# plugwatch.net
KiCad netlist of a schematic drawn in EAGLE
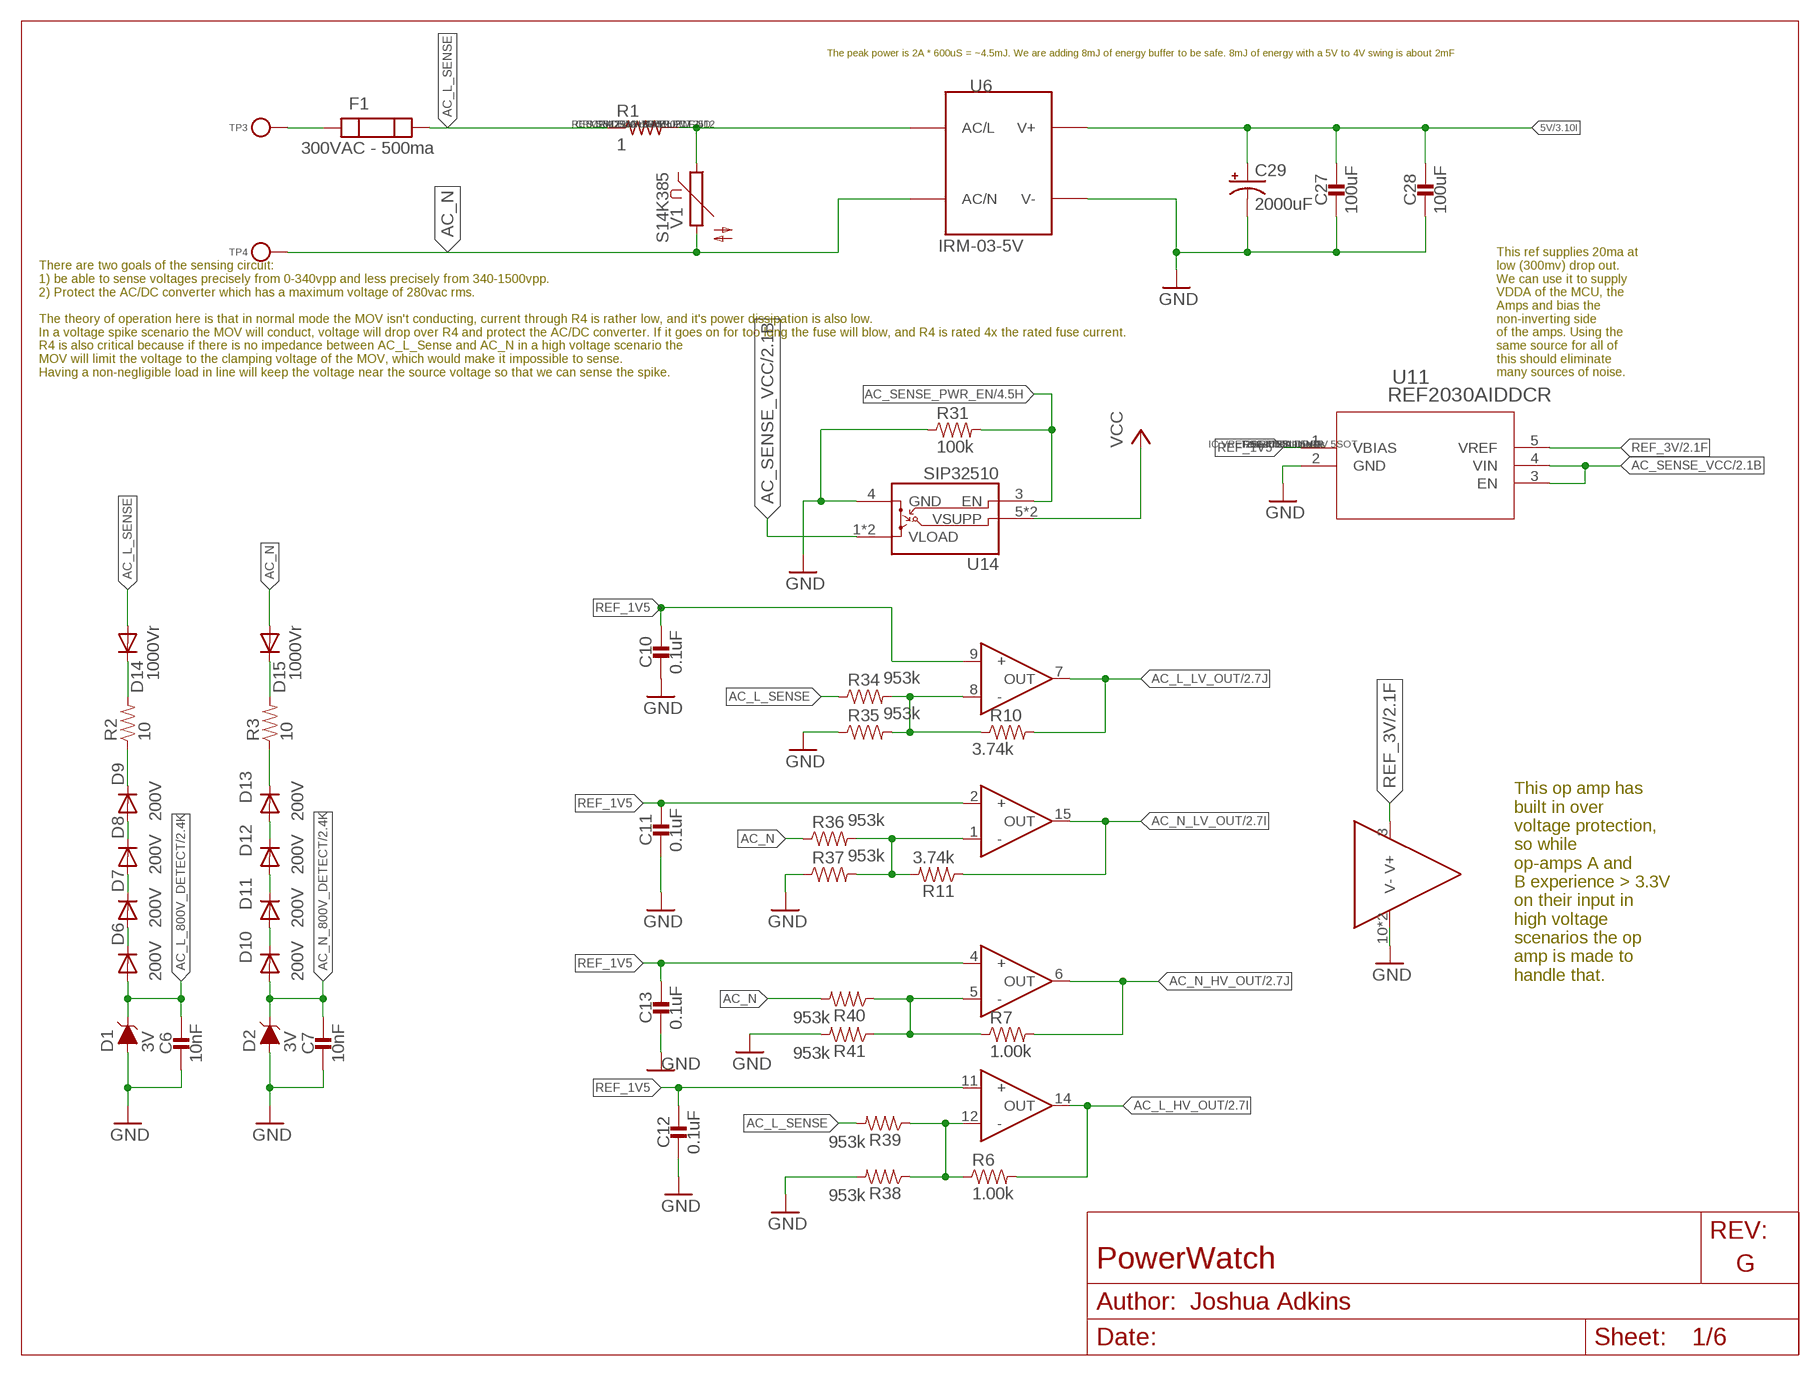
[diagram p0: schematic, sheet 1]
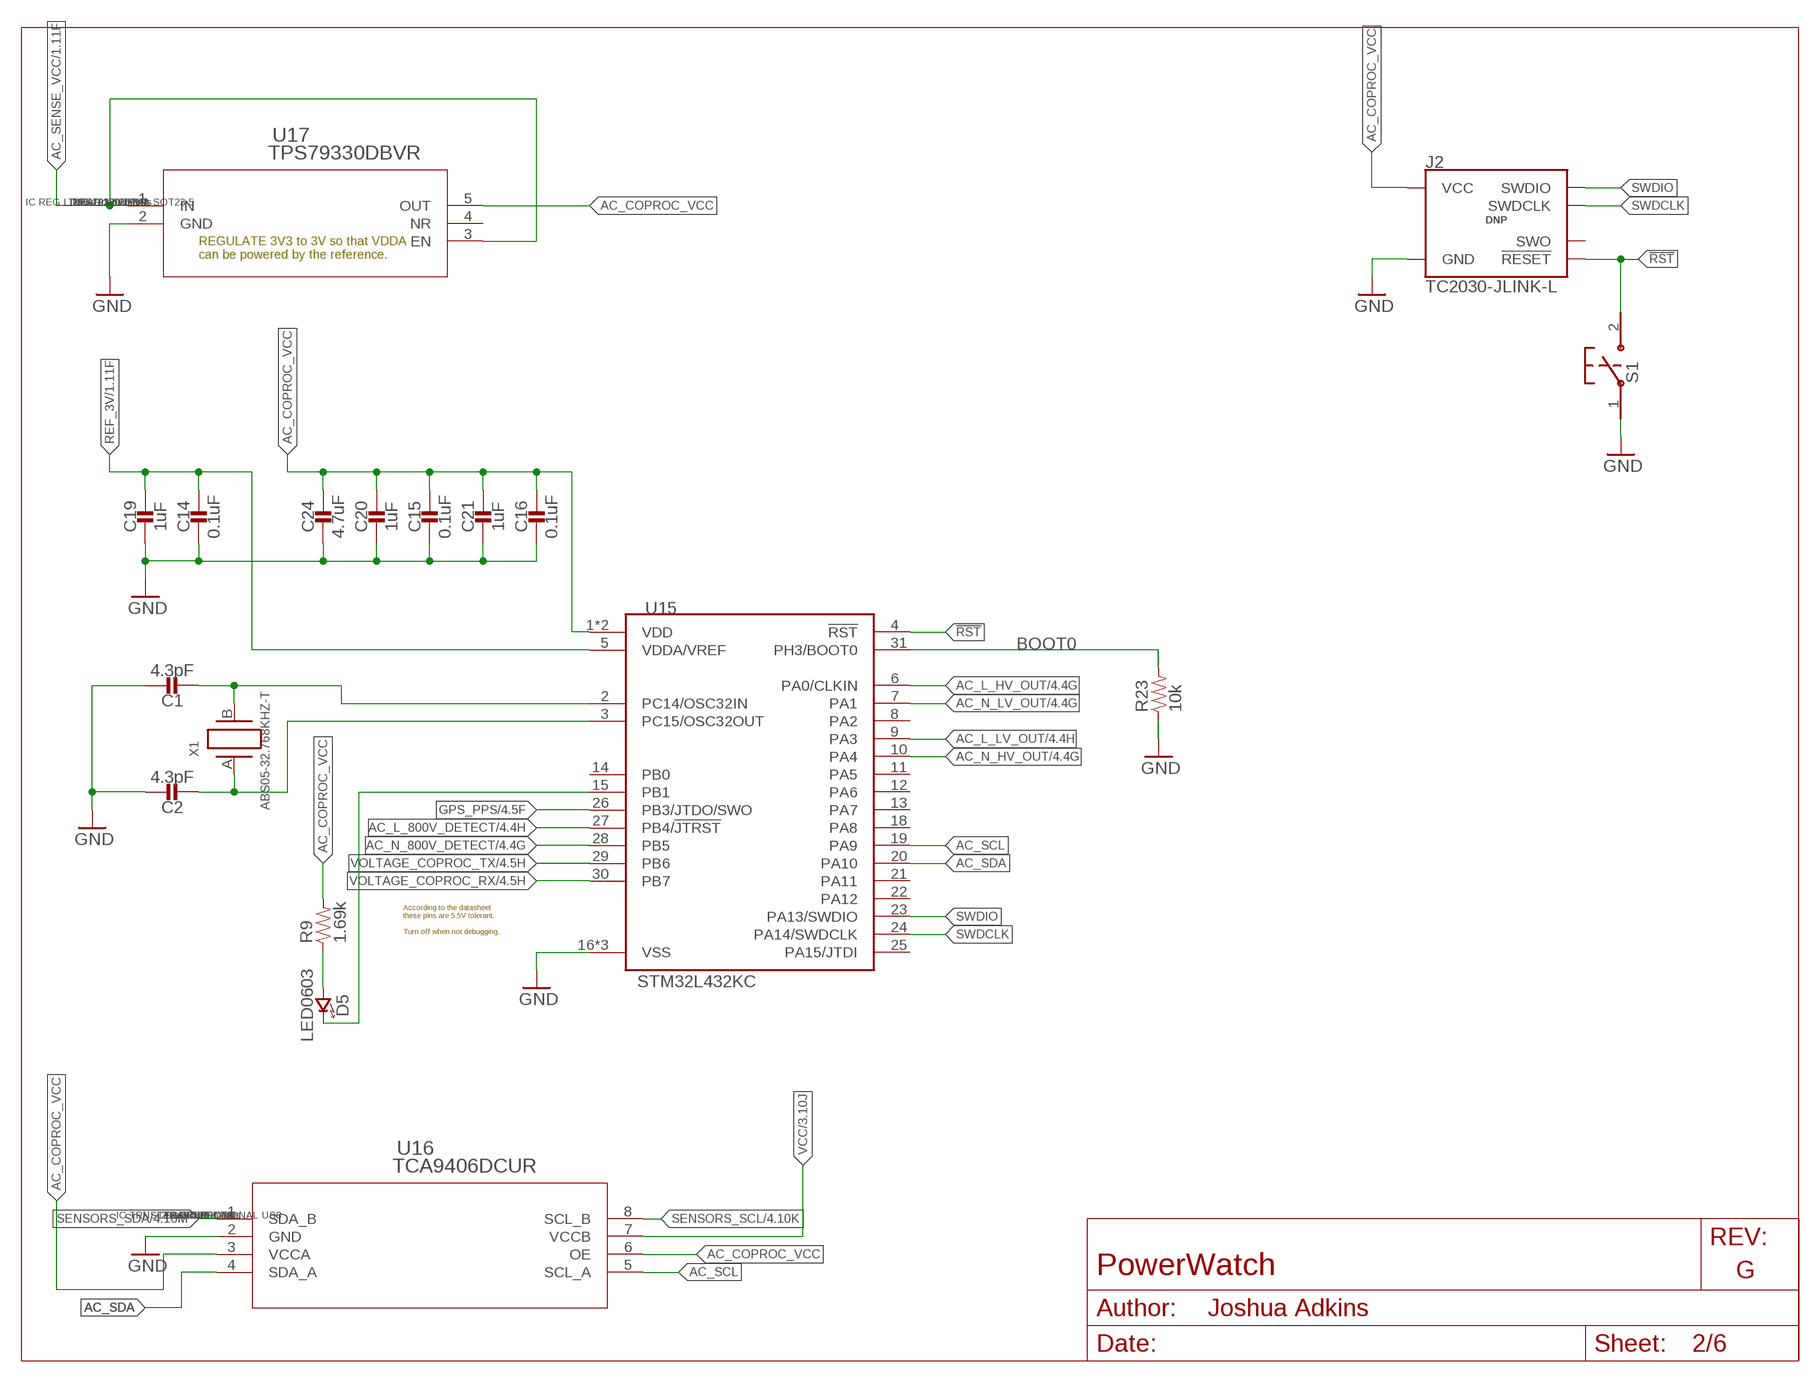
[diagram p1: schematic, sheet 2]
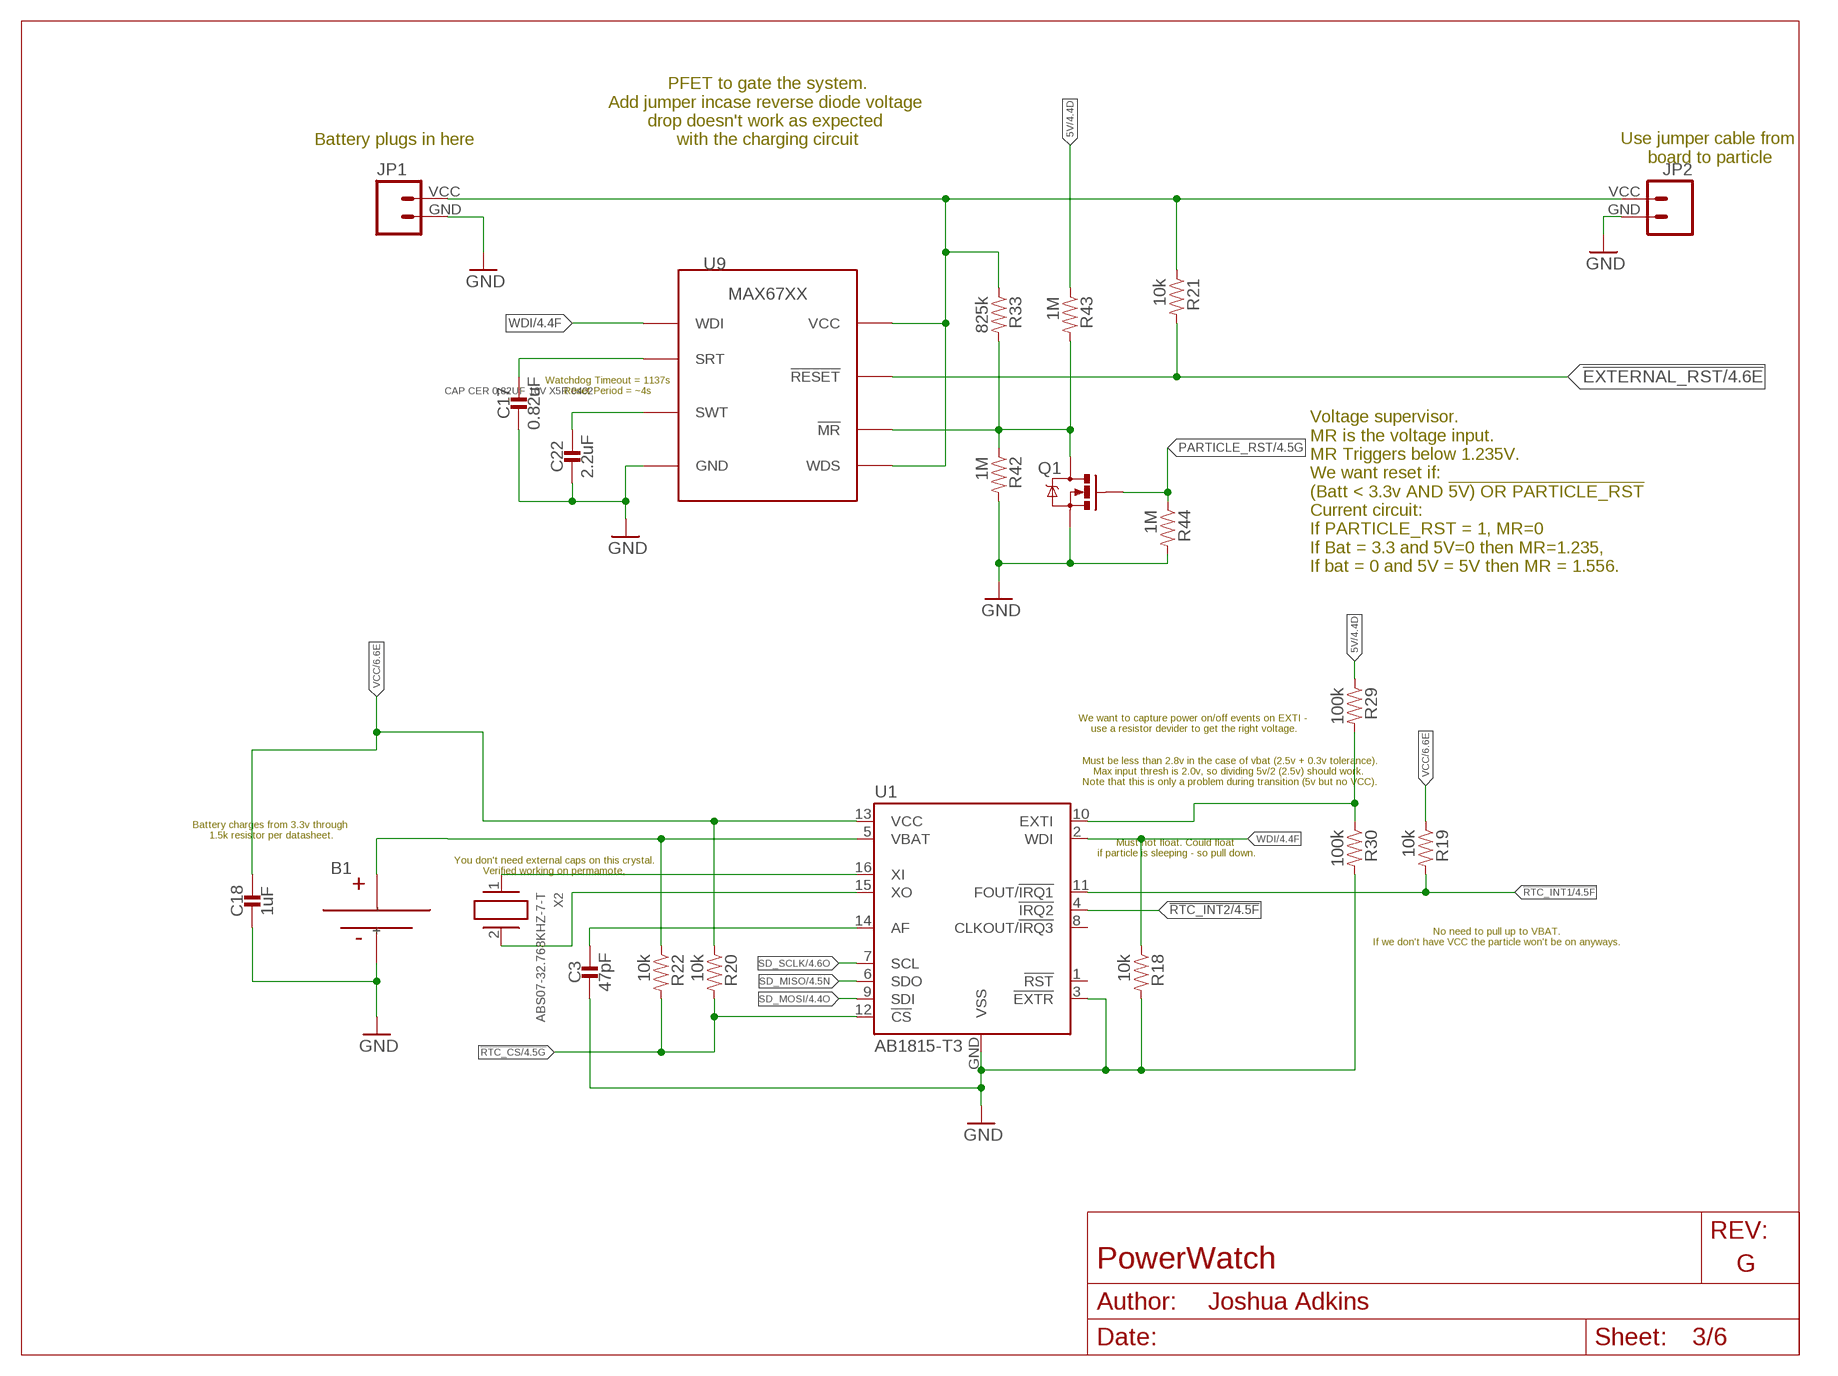
[diagram p2: schematic, sheet 3]
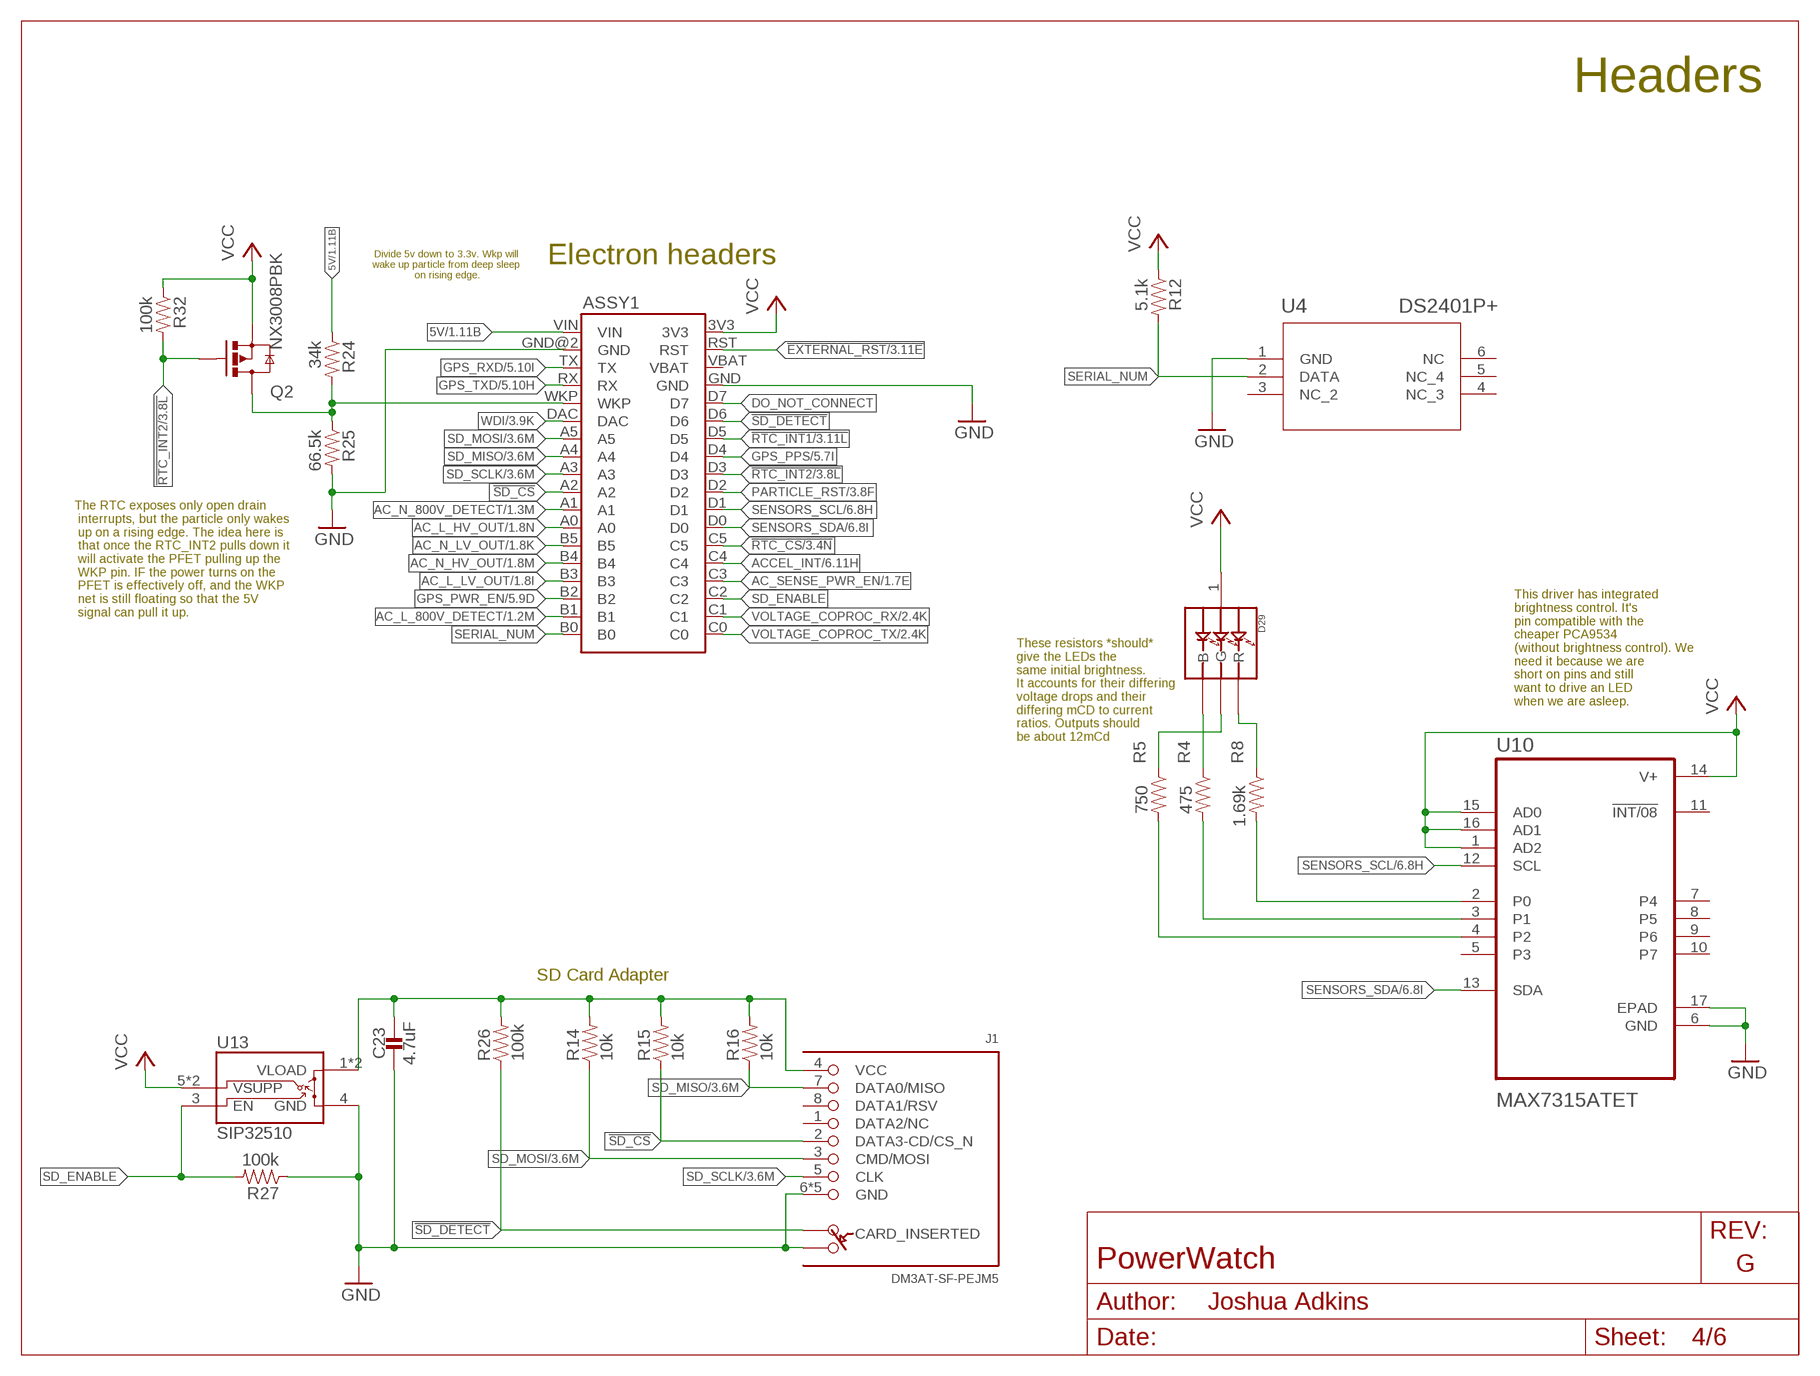
[diagram p3: schematic, sheet 4]
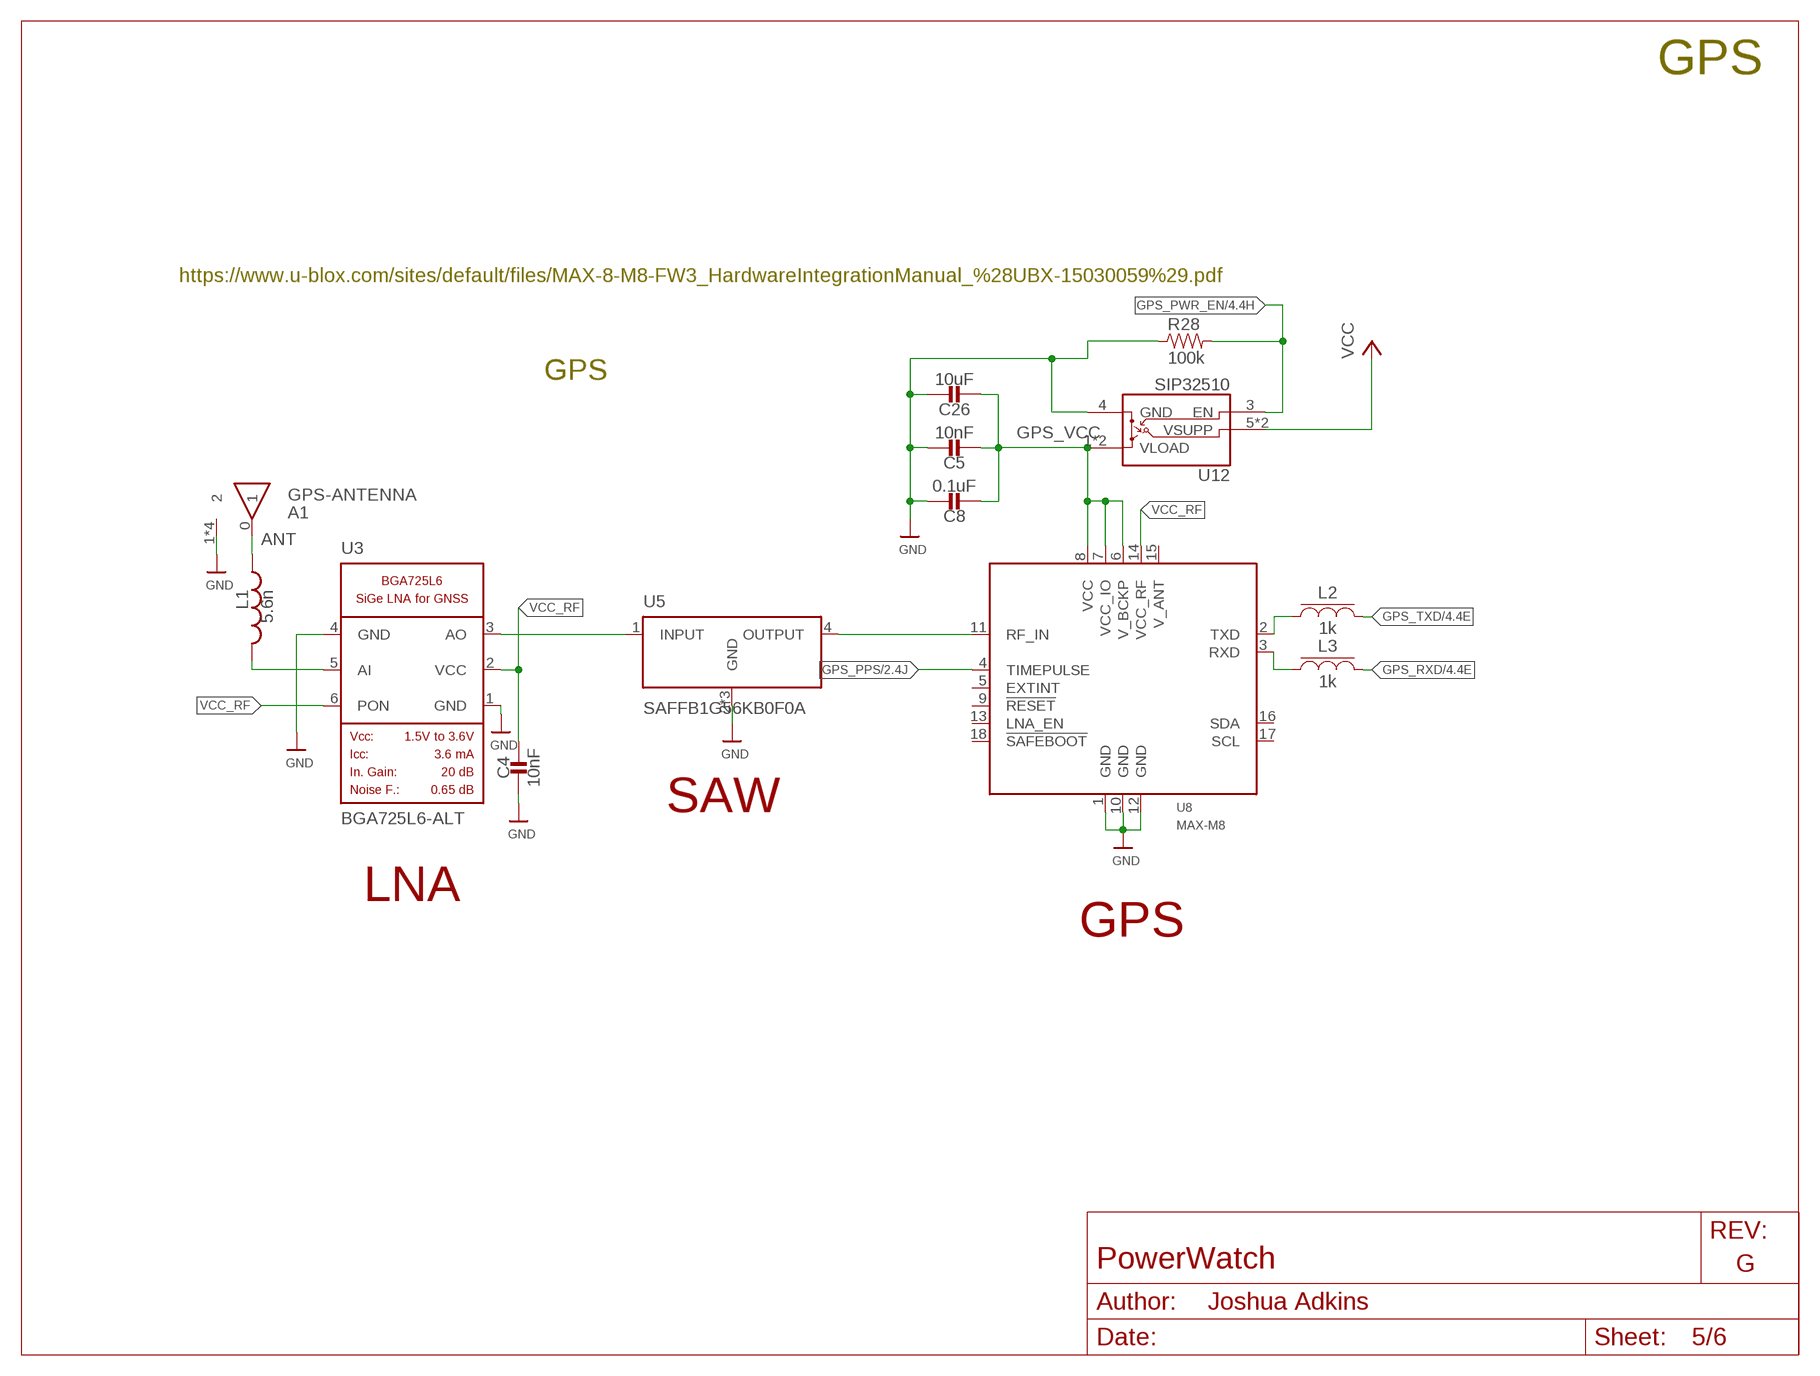
[diagram p4: schematic, sheet 5]
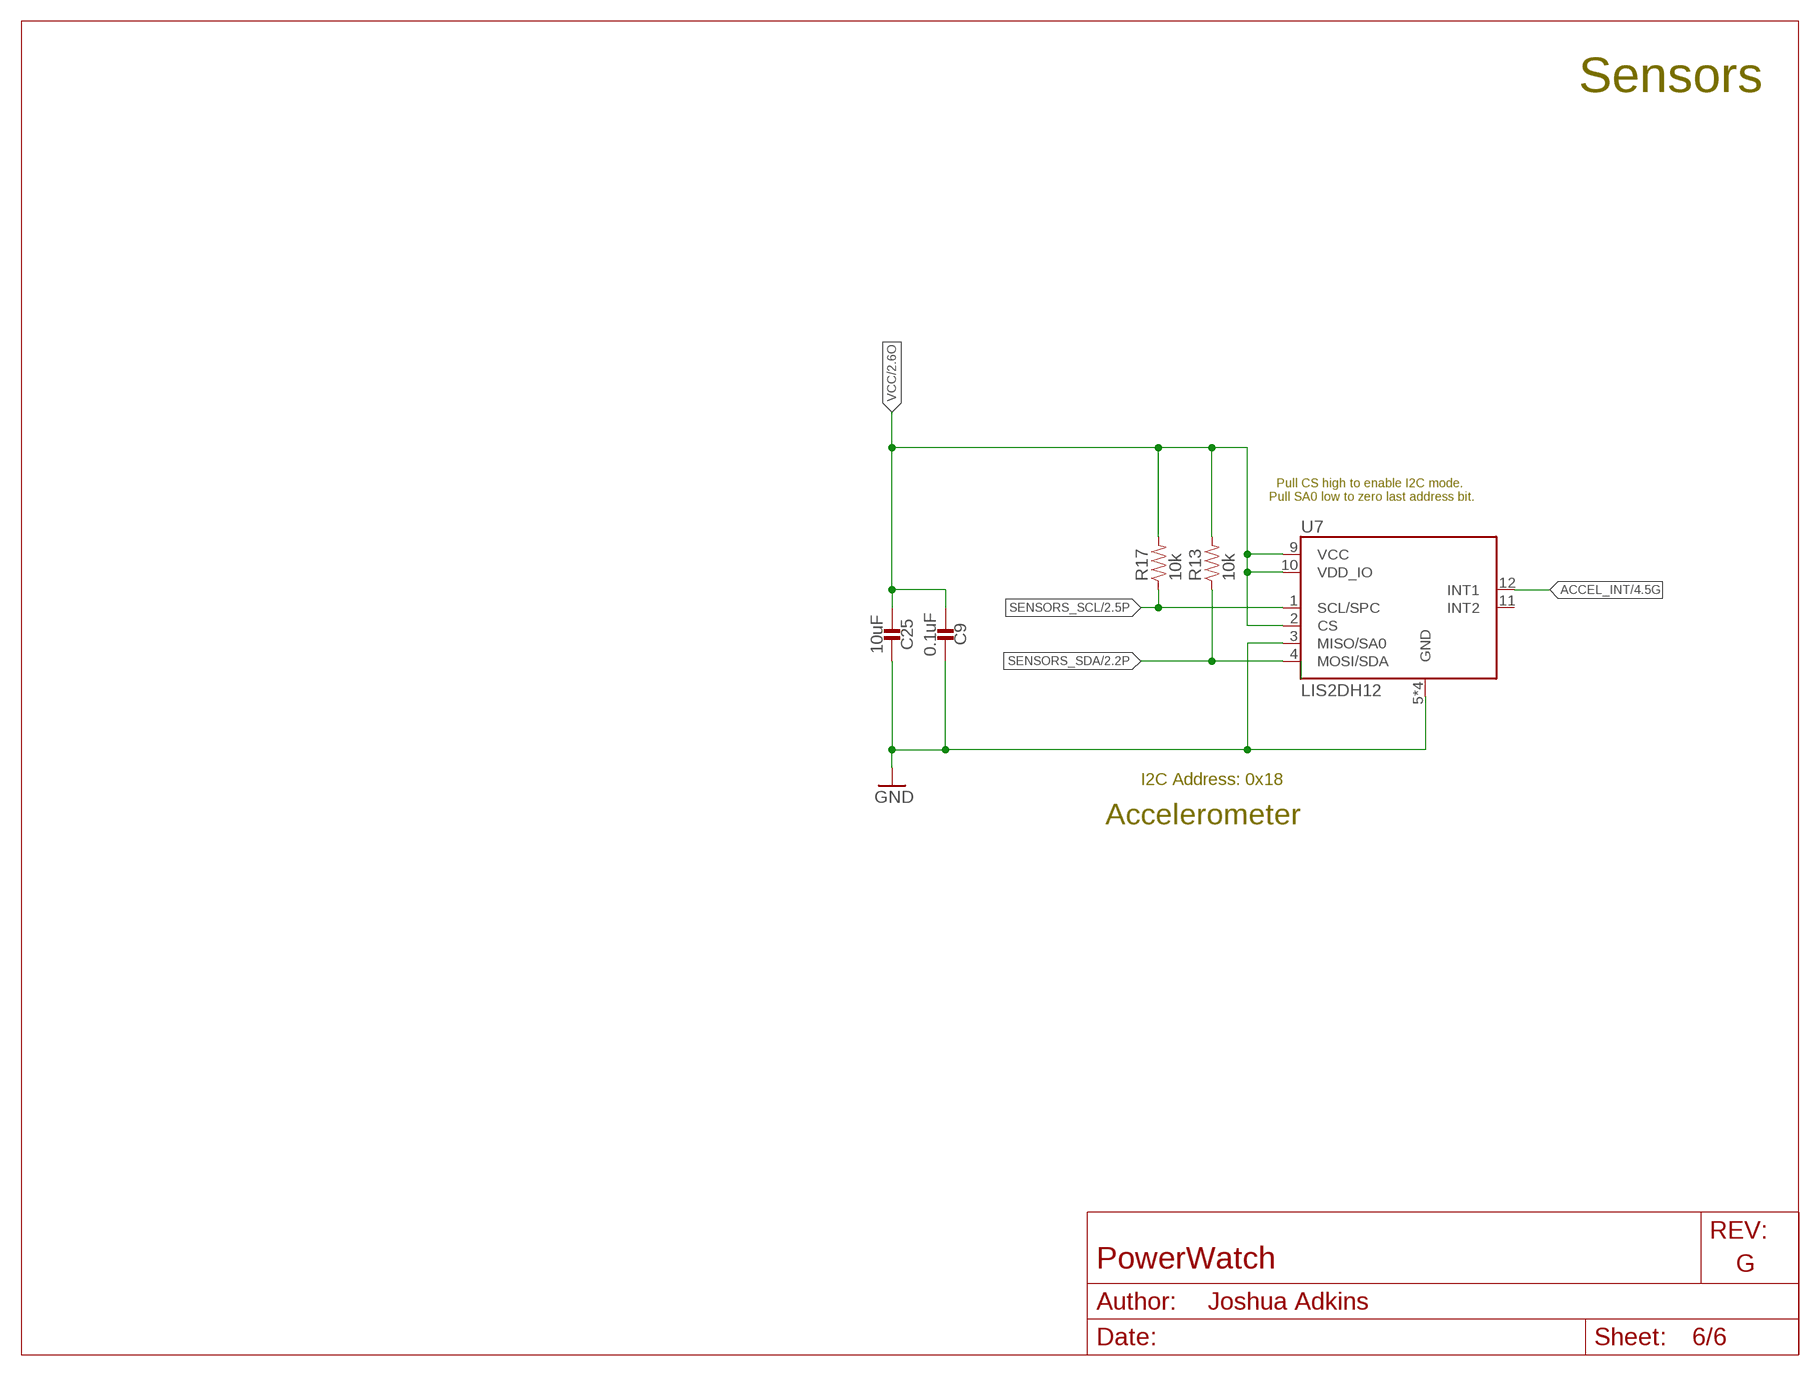
[diagram p5: schematic, sheet 6]

(export (version "E")
  (design (tool "Eeschema 10.0.6"))
  (components
    (comp (ref "ASSY1")
      (value "ELECTRON")
      (footprint "eagle-import:ELECTRON_SINGLE-ROW")
      (description "18 Position header")
      (fields (field (name "MANUFACTURER") "Sullins") (field (name "MPN") "PPPC181LFBN-RC"))
      (libsource (lib "eagle-import") (part "ELECTRON"))
    )
    (comp (ref "C23")
      (value "4.7uF")
      (footprint "eagle-import:0402_CAP")
      (description "CAP CER 4.7UF 6.3V X5R 0402")
      (fields (field (name "MANUFACTURER") "TDK Corporation ") (field (name "MPN") "C1005X5R0J475K050BC "))
      (libsource (lib "eagle-import") (part "CAPACITOR0402_CAP"))
    )
    (comp (ref "D29")
      (value "SML-LX0404SIUPGUSB")
      (footprint "eagle-import:1MM_SQ_4PAD")
      (fields (field (name "MANUFACTURER") "Lumex Opto"))
      (libsource (lib "eagle-import") (part "SML-LX0404SIUPGUSB"))
    )
    (comp (ref "J1")
      (value "DM3AT-SF-PEJM5")
      (footprint "eagle-import:DM3AT-SF-PEJM5")
      (fields (field (name "MANUFACTURER") "Hirose Electric Co Ltd"))
      (libsource (lib "eagle-import") (part "DM3AT-SF-PEJM5"))
    )
    (comp (ref "Q2")
      (value "NX3008PBK")
      (footprint "eagle-import:SOT23-3")
      (fields (field (name "MANUFACTURER") "Nexperia") (field (name "MPN") "NX3008PBK,215"))
      (libsource (lib "eagle-import") (part "NX3008PBK"))
    )
    (comp (ref "R4")
      (value "475")
      (footprint "eagle-import:0402_RES")
      (description "RES 475 OHM 1% 1/16W 0402")
      (fields (field (name "MANUFACTURER") "Stackpole Electronics Inc") (field (name "MPN") "RMCF0402FT475R"))
      (libsource (lib "eagle-import") (part "RESISTOR0402_RES"))
    )
    (comp (ref "R5")
      (value "750")
      (footprint "eagle-import:0402_RES")
      (description "RES SMD 750 OHM 1% 1/10W 0402")
      (fields
        (field (name "MANUFACTURER") "Panasonic Electronic Components")
        (field (name "MPN") "ERJ-2RKF7500X")
      )
      (libsource (lib "eagle-import") (part "RESISTOR0402_RES"))
    )
    (comp (ref "R8")
      (value "1.69k")
      (footprint "eagle-import:0402_RES")
      (description "RES SMD 1.69K OHM 1% 1/16W 0402")
      (fields (field (name "MANUFACTURER") "Yageo") (field (name "MPN") "RC0402FR-071K69L"))
      (libsource (lib "eagle-import") (part "RESISTOR0402_RES"))
    )
    (comp (ref "R12")
      (value "5.1k")
      (footprint "eagle-import:0402_RES")
      (description "RES SMD 5.1K OHM 1% 1/10W 0402")
      (fields
        (field (name "MANUFACTURER") "Panasonic Electronic Components")
        (field (name "MPN") "ERJ-2RKF5101X")
      )
      (libsource (lib "eagle-import") (part "RESISTOR0402_RES"))
    )
    (comp (ref "R14")
      (value "10k")
      (footprint "eagle-import:0402_RES")
      (description "RES SMD 10K OHM 1% 1/16W 0402")
      (fields
        (field (name "MANUFACTURER") "Stackpole Electronics Inc. ")
        (field (name "MPN") "RMCF0402FT10K0 ")
      )
      (libsource (lib "eagle-import") (part "RESISTOR0402_RES"))
    )
    (comp (ref "R15")
      (value "10k")
      (footprint "eagle-import:0402_RES")
      (description "RES SMD 10K OHM 1% 1/16W 0402")
      (fields
        (field (name "MANUFACTURER") "Stackpole Electronics Inc. ")
        (field (name "MPN") "RMCF0402FT10K0 ")
      )
      (libsource (lib "eagle-import") (part "RESISTOR0402_RES"))
    )
    (comp (ref "R16")
      (value "10k")
      (footprint "eagle-import:0402_RES")
      (description "RES SMD 10K OHM 1% 1/16W 0402")
      (fields
        (field (name "MANUFACTURER") "Stackpole Electronics Inc. ")
        (field (name "MPN") "RMCF0402FT10K0 ")
      )
      (libsource (lib "eagle-import") (part "RESISTOR0402_RES"))
    )
    (comp (ref "R24")
      (value "34k")
      (footprint "eagle-import:0402_RES")
      (description "RES SMD 34K OHM 1% 1/10W 0402")
      (fields
        (field (name "MANUFACTURER") "Panasonic Electronic Components")
        (field (name "MPN") "ERJ-2RKF3402X")
      )
      (libsource (lib "eagle-import") (part "RESISTOR0402_RES"))
    )
    (comp (ref "R25")
      (value "66.5k")
      (footprint "eagle-import:0402_RES")
      (description "RES SMD 66.5K OHM 1% 1/16W 0402")
      (fields (field (name "MANUFACTURER") "Yageo") (field (name "MPN") "RC0402FR-0766K5L"))
      (libsource (lib "eagle-import") (part "RESISTOR0402_RES"))
    )
    (comp (ref "R26")
      (value "100k")
      (footprint "eagle-import:0402_RES")
      (description "RES SMD 100K OHM 1% 1/16W 0402")
      (fields (field (name "MANUFACTURER") "Yageo") (field (name "MPN") "RC0402FR-07100KL"))
      (libsource (lib "eagle-import") (part "RESISTOR0402_RES"))
    )
    (comp (ref "R27")
      (value "100k")
      (footprint "eagle-import:0402_RES")
      (description "RES SMD 100K OHM 1% 1/16W 0402")
      (fields (field (name "MANUFACTURER") "Yageo") (field (name "MPN") "RC0402FR-07100KL"))
      (libsource (lib "eagle-import") (part "RESISTOR0402_RES"))
    )
    (comp (ref "R32")
      (value "100k")
      (footprint "eagle-import:0402_RES")
      (description "RES SMD 100K OHM 1% 1/16W 0402")
      (fields (field (name "MANUFACTURER") "Yageo") (field (name "MPN") "RC0402FR-07100KL"))
      (libsource (lib "eagle-import") (part "RESISTOR0402_RES"))
    )
    (comp (ref "U4")
      (value "DS2401P+")
      (footprint "eagle-import:21-0382")
      (fields (field (name "MANUFACTURER") "Maxim Integrated") (field (name "SPICEPREFIX") "X"))
      (libsource (lib "eagle-import") (part "DS2401P+"))
    )
    (comp (ref "U10")
      (value "MAX7315ATET")
      (footprint "eagle-import:QFN50P300X300X80-17N")
      (description "IC I/O EXPANDER I2C 8B 16TQFN")
      (fields
        (field (name "DIGI-KEY_PART_NUMBER") "MAX7315ATE+-ND")
        (field (name "MF") "Maxim Integrated")
        (field (name "MP") "MAX7315ATE+")
        (field (name "DIGIKEY") "MAX7315ATE+-ND")
        (field (name "MANUFACTURER") "Maxim Integrated")
        (field (name "MPN") "MAX7315ATE+")
      )
      (libsource (lib "eagle-import") (part "MAX7315ATET"))
    )
    (comp (ref "U13")
      (value "SIP32510")
      (footprint "eagle-import:TSOT23-6")
      (fields (field (name "MANUFACTURER") "Vishay") (field (name "MPN") "SIP32510DT-T1-GE3"))
      (libsource (lib "eagle-import") (part "SIP32510"))
    )
    (comp (ref "C1")
      (value "4.3pF")
      (footprint "eagle-import:0402_CAP")
      (description "CAP CER 4.3PF 50V C0G/NP0 0402")
      (fields
        (field (name "MANUFACTURER") "Murata Electronics North America")
        (field (name "MPN") "GJM1555C1H4R3CB01D")
      )
      (libsource (lib "eagle-import") (part "CAPACITOR0402_CAP"))
    )
    (comp (ref "C2")
      (value "4.3pF")
      (footprint "eagle-import:0402_CAP")
      (description "CAP CER 4.3PF 50V C0G/NP0 0402")
      (fields
        (field (name "MANUFACTURER") "Murata Electronics North America")
        (field (name "MPN") "GJM1555C1H4R3CB01D")
      )
      (libsource (lib "eagle-import") (part "CAPACITOR0402_CAP"))
    )
    (comp (ref "C14")
      (value "0.1uF")
      (footprint "eagle-import:0402_CAP")
      (description "CAP CER 0.1UF 10V X5R 0402")
      (fields (field (name "MANUFACTURER") "Yageo") (field (name "MPN") "CC0402KRX5R6BB104"))
      (libsource (lib "eagle-import") (part "CAPACITOR0402_CAP"))
    )
    (comp (ref "C15")
      (value "0.1uF")
      (footprint "eagle-import:0402_CAP")
      (description "CAP CER 0.1UF 10V X5R 0402")
      (fields (field (name "MANUFACTURER") "Yageo") (field (name "MPN") "CC0402KRX5R6BB104"))
      (libsource (lib "eagle-import") (part "CAPACITOR0402_CAP"))
    )
    (comp (ref "C16")
      (value "0.1uF")
      (footprint "eagle-import:0402_CAP")
      (description "CAP CER 0.1UF 10V X5R 0402")
      (fields (field (name "MANUFACTURER") "Yageo") (field (name "MPN") "CC0402KRX5R6BB104"))
      (libsource (lib "eagle-import") (part "CAPACITOR0402_CAP"))
    )
    (comp (ref "C19")
      (value "1uF")
      (footprint "eagle-import:0402_CAP")
      (description "CAP CER 1UF 10V X7S 0402")
      (fields
        (field (name "MANUFACTURER") "Murata Electronics North America")
        (field (name "MPN") "GCM155C71A105KE38D")
      )
      (libsource (lib "eagle-import") (part "CAPACITOR0402_CAP"))
    )
    (comp (ref "C20")
      (value "1uF")
      (footprint "eagle-import:0402_CAP")
      (description "CAP CER 1UF 10V X7S 0402")
      (fields
        (field (name "MANUFACTURER") "Murata Electronics North America")
        (field (name "MPN") "GCM155C71A105KE38D")
      )
      (libsource (lib "eagle-import") (part "CAPACITOR0402_CAP"))
    )
    (comp (ref "C21")
      (value "1uF")
      (footprint "eagle-import:0402_CAP")
      (description "CAP CER 1UF 10V X7S 0402")
      (fields
        (field (name "MANUFACTURER") "Murata Electronics North America")
        (field (name "MPN") "GCM155C71A105KE38D")
      )
      (libsource (lib "eagle-import") (part "CAPACITOR0402_CAP"))
    )
    (comp (ref "C24")
      (value "4.7uF")
      (footprint "eagle-import:0402_CAP")
      (description "CAP CER 4.7UF 6.3V X5R 0402")
      (fields (field (name "MANUFACTURER") "TDK Corporation ") (field (name "MPN") "C1005X5R0J475K050BC "))
      (libsource (lib "eagle-import") (part "CAPACITOR0402_CAP"))
    )
    (comp (ref "D5")
      (value "LED0603")
      (footprint "eagle-import:LED-0603")
      (description "LED RED DIFFUSED 1608 SMD")
      (fields
        (field (name "DIGIKEY") "SML-D12U1WT86CT-ND")
        (field (name "MANUFACTURER") "Rohm Semiconductor")
        (field (name "MPN") "SML-D12U1WT86")
      )
      (libsource (lib "eagle-import") (part "LED0603"))
    )
    (comp (ref "J2")
      (value "TC2030-JLINK-L")
      (footprint "eagle-import:TC2030-IDC")
      (fields (field (name "DIGIKEY") "DNP") (field (name "MANUFACTURER") "DNP") (field (name "MPN") "DNP"))
      (libsource (lib "eagle-import") (part "TC2030-JLINK-L"))
    )
    (comp (ref "R9")
      (value "1.69k")
      (footprint "eagle-import:0402_RES")
      (description "RES SMD 1.69K OHM 1% 1/16W 0402")
      (fields (field (name "MANUFACTURER") "Yageo") (field (name "MPN") "RC0402FR-071K69L"))
      (libsource (lib "eagle-import") (part "RESISTOR0402_RES"))
    )
    (comp (ref "R23")
      (value "10k")
      (footprint "eagle-import:0402_RES")
      (description "RES SMD 10K OHM 1% 1/16W 0402")
      (fields
        (field (name "MANUFACTURER") "Stackpole Electronics Inc.  ")
        (field (name "MPN") "RMCF0402FT10K0  ")
      )
      (libsource (lib "eagle-import") (part "RESISTOR0402_RES"))
    )
    (comp (ref "S1")
      (value "B3U-1000P")
      (footprint "eagle-import:B3U-1000P")
      (fields (field (name "MANUFACTURER") "Omron"))
      (libsource (lib "eagle-import") (part "B3U-1000P"))
    )
    (comp (ref "U15")
      (value "STM32L432KC")
      (footprint "eagle-import:UQFN-32")
      (fields (field (name "MANUFACTURER") "STMicroelectronics") (field (name "MPN") "STM32L432KCU6"))
      (libsource (lib "eagle-import") (part "STM32L432KC"))
    )
    (comp (ref "U16")
      (value "TCA9406DCUR")
      (footprint "eagle-import:DCU8")
      (description "IC TRNSLTR BIDIRECTIONAL US8")
      (fields
        (field (name "DIGIKEY") "296-28109-1-ND")
        (field (name "MANUFACTURER") "Texas Instruments")
        (field (name "MPN") "TCA9406DCUR")
      )
      (libsource (lib "eagle-import") (part "TCA9406DCUR"))
    )
    (comp (ref "U17")
      (value "TPS79330DBVR")
      (footprint "eagle-import:DBV5")
      (description "IC REG LINEAR 3V 200MA SOT23-5")
      (fields
        (field (name "DIGIKEY") "296-12159-1-ND")
        (field (name "MANUFACTURER") "Texas Instruments")
        (field (name "MPN") "TPS79330DBVR")
      )
      (libsource (lib "eagle-import") (part "TPS79330DBVR"))
    )
    (comp (ref "X1")
      (value "ABS05-32.768KHZ-T")
      (footprint "eagle-import:ABS05")
      (fields (field (name "MANUFACTURER") "Abracon"))
      (libsource (lib "eagle-import") (part "ABS05-32.768KHZ-T"))
    )
    (comp (ref "B1")
      (value "MS518SE")
      (footprint "eagle-import:MS518SE-FL35E")
      (fields (field (name "MANUFACTURER") "Seiko") (field (name "MPN") "MS518SE-FL35E"))
      (libsource (lib "eagle-import") (part "MS518SE"))
    )
    (comp (ref "C3")
      (value "47pF")
      (footprint "eagle-import:0402_CAP")
      (description "CAP CER 47PF 100V C0G/NP0 0402")
      (fields
        (field (name "MANUFACTURER") "Murata Electronics North America")
        (field (name "MPN") "GRM1555C2A470JA01D")
      )
      (libsource (lib "eagle-import") (part "CAPACITOR0402_CAP"))
    )
    (comp (ref "C17")
      (value "0.82uF")
      (footprint "eagle-import:0402_CAP")
      (description "CAP CER 0.82UF 10V X5R 0402")
      (fields (field (name "MANUFACTURER") "Yageo") (field (name "MPN") "CC0402KRX5R6BB824"))
      (libsource (lib "eagle-import") (part "CAPACITOR0402_CAP"))
    )
    (comp (ref "C18")
      (value "1uF")
      (footprint "eagle-import:0402_CAP")
      (description "CAP CER 1UF 10V X7S 0402")
      (fields
        (field (name "MANUFACTURER") "Murata Electronics North America")
        (field (name "MPN") "GCM155C71A105KE38D")
      )
      (libsource (lib "eagle-import") (part "CAPACITOR0402_CAP"))
    )
    (comp (ref "C22")
      (value "2.2uF")
      (footprint "eagle-import:0402_CAP")
      (fields
        (field (name "MANUFACTURER") "Murata Electronics North America")
        (field (name "MPN") "GRM155C70J225KE11D")
      )
      (libsource (lib "eagle-import") (part "CAPACITOR0402_CAP"))
    )
    (comp (ref "JP1")
      (value "M024UCON-15767")
      (footprint "eagle-import:JST-2-SMD-VERT")
      (description "CONN HEADER PH TOP 2POS 2MM SMD")
      (fields
        (field (name "MANUFACTURER") "JST Sales America Inc.")
        (field (name "MPN") "B2B-PH-SM4-TB(LF)(SN)")
      )
      (libsource (lib "eagle-import") (part "M024UCON-15767"))
    )
    (comp (ref "JP2")
      (value "M024UCON-15767")
      (footprint "eagle-import:JST-2-SMD-VERT")
      (description "CONN HEADER PH TOP 2POS 2MM SMD")
      (fields
        (field (name "MANUFACTURER") "JST Sales America Inc.")
        (field (name "MPN") "B2B-PH-SM4-TB(LF)(SN)")
      )
      (libsource (lib "eagle-import") (part "M024UCON-15767"))
    )
    (comp (ref "Q1")
      (value "MOSFET-NCHANNELSMD")
      (footprint "eagle-import:SOT23-3")
      (description "MOSFET N-CH 60V 115MA SOT23-3")
      (fields
        (field (name "DIGIKEY") "2N7002-FDICT-ND")
        (field (name "MANUFACTURER") "Diodes Incorporated")
        (field (name "MPN") "2N7002-7-F")
      )
      (libsource (lib "eagle-import") (part "MOSFET-NCHANNELSMD"))
    )
    (comp (ref "R18")
      (value "10k")
      (footprint "eagle-import:0402_RES")
      (description "RES SMD 10K OHM 1% 1/16W 0402")
      (fields
        (field (name "MANUFACTURER") "Stackpole Electronics Inc. ")
        (field (name "MPN") "RMCF0402FT10K0 ")
      )
      (libsource (lib "eagle-import") (part "RESISTOR0402_RES"))
    )
    (comp (ref "R19")
      (value "10k")
      (footprint "eagle-import:0402_RES")
      (description "RES SMD 10K OHM 1% 1/16W 0402")
      (fields
        (field (name "MANUFACTURER") "Stackpole Electronics Inc. ")
        (field (name "MPN") "RMCF0402FT10K0 ")
      )
      (libsource (lib "eagle-import") (part "RESISTOR0402_RES"))
    )
    (comp (ref "R20")
      (value "10k")
      (footprint "eagle-import:0402_RES")
      (description "RES SMD 10K OHM 1% 1/16W 0402")
      (fields
        (field (name "MANUFACTURER") "Stackpole Electronics Inc. ")
        (field (name "MPN") "RMCF0402FT10K0 ")
      )
      (libsource (lib "eagle-import") (part "RESISTOR0402_RES"))
    )
    (comp (ref "R21")
      (value "10k")
      (footprint "eagle-import:0402_RES")
      (description "RES SMD 10K OHM 1% 1/16W 0402")
      (fields
        (field (name "MANUFACTURER") "Stackpole Electronics Inc. ")
        (field (name "MPN") "RMCF0402FT10K0 ")
      )
      (libsource (lib "eagle-import") (part "RESISTOR0402_RES"))
    )
    (comp (ref "R22")
      (value "10k")
      (footprint "eagle-import:0402_RES")
      (description "RES SMD 10K OHM 1% 1/16W 0402")
      (fields
        (field (name "MANUFACTURER") "Stackpole Electronics Inc. ")
        (field (name "MPN") "RMCF0402FT10K0 ")
      )
      (libsource (lib "eagle-import") (part "RESISTOR0402_RES"))
    )
    (comp (ref "R29")
      (value "100k")
      (footprint "eagle-import:0402_RES")
      (description "RES SMD 100K OHM 1% 1/16W 0402")
      (fields (field (name "MANUFACTURER") "Yageo") (field (name "MPN") "RC0402FR-07100KL"))
      (libsource (lib "eagle-import") (part "RESISTOR0402_RES"))
    )
    (comp (ref "R30")
      (value "100k")
      (footprint "eagle-import:0402_RES")
      (description "RES SMD 100K OHM 1% 1/16W 0402")
      (fields (field (name "MANUFACTURER") "Yageo") (field (name "MPN") "RC0402FR-07100KL"))
      (libsource (lib "eagle-import") (part "RESISTOR0402_RES"))
    )
    (comp (ref "R33")
      (value "825k")
      (footprint "eagle-import:0402_RES")
      (description "RES SMD 825K OHM 1% 1/10W 0402")
      (fields
        (field (name "MANUFACTURER") "Panasonic Electronic Components")
        (field (name "MPN") "ERJ-2RKF8253X")
      )
      (libsource (lib "eagle-import") (part "RESISTOR0402_RES"))
    )
    (comp (ref "R42")
      (value "1M")
      (footprint "eagle-import:0402_RES")
      (description "RES 1M OHM 1% 1/16W 0402")
      (fields
        (field (name "MANUFACTURER") "Stackpole Electronics Inc ")
        (field (name "MPN") "RMCF0402FT1M00 ")
      )
      (libsource (lib "eagle-import") (part "RESISTOR0402_RES"))
    )
    (comp (ref "R43")
      (value "1M")
      (footprint "eagle-import:0402_RES")
      (description "RES 1M OHM 1% 1/16W 0402")
      (fields
        (field (name "MANUFACTURER") "Stackpole Electronics Inc ")
        (field (name "MPN") "RMCF0402FT1M00 ")
      )
      (libsource (lib "eagle-import") (part "RESISTOR0402_RES"))
    )
    (comp (ref "R44")
      (value "1M")
      (footprint "eagle-import:0402_RES")
      (description "RES 1M OHM 1% 1/16W 0402")
      (fields
        (field (name "MANUFACTURER") "Stackpole Electronics Inc ")
        (field (name "MPN") "RMCF0402FT1M00 ")
      )
      (libsource (lib "eagle-import") (part "RESISTOR0402_RES"))
    )
    (comp (ref "U1")
      (value "AB1815-T3")
      (footprint "eagle-import:QFN-16-3MM")
      (fields (field (name "MANUFACTURER") "Abracon"))
      (libsource (lib "eagle-import") (part "AB1815-T3"))
    )
    (comp (ref "U9")
      (value "MAX67XXMAX6749MAX67XX")
      (footprint "eagle-import:SOT-23-8")
      (fields (field (name "MANUFACTURER") "Maxim Integrated") (field (name "MPN") "MAX6749KA+T"))
      (libsource (lib "eagle-import") (part "MAX67XXMAX67XXMAX6749"))
    )
    (comp (ref "X2")
      (value "ABS07-32.768KHZ-7-T")
      (footprint "eagle-import:2-SMD")
      (fields (field (name "MANUFACTURER") "ABRACON") (field (name "MPN") "ABS07-32.768KHZ-7-T "))
      (libsource (lib "eagle-import") (part "ABS07-32.768KHZ-7-T"))
    )
    (comp (ref "C6")
      (value "10nF")
      (footprint "eagle-import:0402_CAP")
      (description "CAP CER 10000PF 16V X7R 0402")
      (fields
        (field (name "MANUFACTURER") "Murata Electronics North America")
        (field (name "MPN") "GRM155R71C103KA01D")
      )
      (libsource (lib "eagle-import") (part "CAPACITOR0402_CAP"))
    )
    (comp (ref "C7")
      (value "10nF")
      (footprint "eagle-import:0402_CAP")
      (description "CAP CER 10000PF 16V X7R 0402")
      (fields
        (field (name "MANUFACTURER") "Murata Electronics North America")
        (field (name "MPN") "GRM155R71C103KA01D")
      )
      (libsource (lib "eagle-import") (part "CAPACITOR0402_CAP"))
    )
    (comp (ref "C10")
      (value "0.1uF")
      (footprint "eagle-import:0402_CAP")
      (description "CAP CER 0.1UF 10V X5R 0402")
      (fields (field (name "MANUFACTURER") "Yageo") (field (name "MPN") "CC0402KRX5R6BB104"))
      (libsource (lib "eagle-import") (part "CAPACITOR0402_CAP"))
    )
    (comp (ref "C11")
      (value "0.1uF")
      (footprint "eagle-import:0402_CAP")
      (description "CAP CER 0.1UF 10V X5R 0402")
      (fields (field (name "MANUFACTURER") "Yageo") (field (name "MPN") "CC0402KRX5R6BB104"))
      (libsource (lib "eagle-import") (part "CAPACITOR0402_CAP"))
    )
    (comp (ref "C12")
      (value "0.1uF")
      (footprint "eagle-import:0402_CAP")
      (description "CAP CER 0.1UF 10V X5R 0402")
      (fields (field (name "MANUFACTURER") "Yageo") (field (name "MPN") "CC0402KRX5R6BB104"))
      (libsource (lib "eagle-import") (part "CAPACITOR0402_CAP"))
    )
    (comp (ref "C13")
      (value "0.1uF")
      (footprint "eagle-import:0402_CAP")
      (description "CAP CER 0.1UF 10V X5R 0402")
      (fields (field (name "MANUFACTURER") "Yageo") (field (name "MPN") "CC0402KRX5R6BB104"))
      (libsource (lib "eagle-import") (part "CAPACITOR0402_CAP"))
    )
    (comp (ref "C27")
      (value "100uF")
      (footprint "eagle-import:1210_CAP")
      (description "CAP CER 100UF 6.3V X7S 1210")
      (fields
        (field (name "MANUFACTURER") "Murata Electronics North America")
        (field (name "MPN") "GRM32EC70J107ME15L")
      )
      (libsource (lib "eagle-import") (part "CAPACITOR1210_CAP"))
    )
    (comp (ref "C28")
      (value "100uF")
      (footprint "eagle-import:1210_CAP")
      (description "CAP CER 100UF 6.3V X7S 1210")
      (fields
        (field (name "MANUFACTURER") "Murata Electronics North America")
        (field (name "MPN") "GRM32EC70J107ME15L")
      )
      (libsource (lib "eagle-import") (part "CAPACITOR1210_CAP"))
    )
    (comp (ref "C29")
      (value "2000uF")
      (footprint "eagle-import:E5-10,5")
      (description "CAP ALUM 2000UF 20% 6.3V T/H")
      (fields
        (field (name "MANUFACTURER") "Panasonic Electronic Components")
        (field (name "MPN") "EEU-FS0J202B")
      )
      (libsource (lib "eagle-import") (part "CPOL-USE5-10.5"))
    )
    (comp (ref "D1")
      (value "3V")
      (footprint "eagle-import:SOD-323")
      (description "DIODE ZENER 3V 300MW SOD323")
      (fields
        (field (name "DIGIKEY") "MM3Z3V0ST1GOSCT-ND")
        (field (name "MANUFACTURER") "ON Semiconductor")
        (field (name "MPN") "MM3Z3V0ST1G")
      )
      (libsource (lib "eagle-import") (part "DIODE-ZENER-MM3Z3V3T1G"))
    )
    (comp (ref "D2")
      (value "3V")
      (footprint "eagle-import:SOD-323")
      (description "DIODE ZENER 3V 300MW SOD323")
      (fields
        (field (name "DIGIKEY") "MM3Z3V0ST1GOSCT-ND")
        (field (name "MANUFACTURER") "ON Semiconductor")
        (field (name "MPN") "MM3Z3V0ST1G")
      )
      (libsource (lib "eagle-import") (part "DIODE-ZENER-MM3Z3V3T1G"))
    )
    (comp (ref "D6")
      (value "200V")
      (footprint "eagle-import:DO214AA")
      (description "DIODE ZENER 200V 3W DO214AA")
      (fields
        (field (name "DIGIKEY") "1PGSMB5956R5GCT-ND")
        (field (name "MANUFACTURER") "Taiwan Semiconductor Corporation")
        (field (name "MPN") "1PGSMB5956 R5G")
      )
      (libsource (lib "eagle-import") (part "DIODE-DO214AA"))
    )
    (comp (ref "D7")
      (value "200V")
      (footprint "eagle-import:DO214AA")
      (description "DIODE ZENER 200V 3W DO214AA")
      (fields
        (field (name "DIGIKEY") "1PGSMB5956R5GCT-ND")
        (field (name "MANUFACTURER") "Taiwan Semiconductor Corporation")
        (field (name "MPN") "1PGSMB5956 R5G")
      )
      (libsource (lib "eagle-import") (part "DIODE-DO214AA"))
    )
    (comp (ref "D8")
      (value "200V")
      (footprint "eagle-import:DO214AA")
      (description "DIODE ZENER 200V 3W DO214AA")
      (fields
        (field (name "DIGIKEY") "1PGSMB5956R5GCT-ND")
        (field (name "MANUFACTURER") "Taiwan Semiconductor Corporation")
        (field (name "MPN") "1PGSMB5956 R5G")
      )
      (libsource (lib "eagle-import") (part "DIODE-DO214AA"))
    )
    (comp (ref "D9")
      (value "200V")
      (footprint "eagle-import:DO214AA")
      (description "DIODE ZENER 200V 3W DO214AA")
      (fields
        (field (name "DIGIKEY") "1PGSMB5956R5GCT-ND")
        (field (name "MANUFACTURER") "Taiwan Semiconductor Corporation")
        (field (name "MPN") "1PGSMB5956 R5G")
      )
      (libsource (lib "eagle-import") (part "DIODE-DO214AA"))
    )
    (comp (ref "D10")
      (value "200V")
      (footprint "eagle-import:DO214AA")
      (description "DIODE ZENER 200V 3W DO214AA")
      (fields
        (field (name "DIGIKEY") "1PGSMB5956R5GCT-ND")
        (field (name "MANUFACTURER") "Taiwan Semiconductor Corporation")
        (field (name "MPN") "1PGSMB5956 R5G")
      )
      (libsource (lib "eagle-import") (part "DIODE-DO214AA"))
    )
    (comp (ref "D11")
      (value "200V")
      (footprint "eagle-import:DO214AA")
      (description "DIODE ZENER 200V 3W DO214AA")
      (fields
        (field (name "DIGIKEY") "1PGSMB5956R5GCT-ND")
        (field (name "MANUFACTURER") "Taiwan Semiconductor Corporation")
        (field (name "MPN") "1PGSMB5956 R5G")
      )
      (libsource (lib "eagle-import") (part "DIODE-DO214AA"))
    )
    (comp (ref "D12")
      (value "200V")
      (footprint "eagle-import:DO214AA")
      (description "DIODE ZENER 200V 3W DO214AA")
      (fields
        (field (name "DIGIKEY") "1PGSMB5956R5GCT-ND")
        (field (name "MANUFACTURER") "Taiwan Semiconductor Corporation")
        (field (name "MPN") "1PGSMB5956 R5G")
      )
      (libsource (lib "eagle-import") (part "DIODE-DO214AA"))
    )
    (comp (ref "D13")
      (value "200V")
      (footprint "eagle-import:DO214AA")
      (description "DIODE ZENER 200V 3W DO214AA")
      (fields
        (field (name "DIGIKEY") "1PGSMB5956R5GCT-ND")
        (field (name "MANUFACTURER") "Taiwan Semiconductor Corporation")
        (field (name "MPN") "1PGSMB5956 R5G")
      )
      (libsource (lib "eagle-import") (part "DIODE-DO214AA"))
    )
    (comp (ref "D14")
      (value "1000Vr")
      (footprint "eagle-import:DO214AC")
      (description "DIODE GEN PURP 1KV 1A SMA")
      (fields
        (field (name "DIGIKEY") "S1M-FDICT-ND")
        (field (name "MANUFACTURER") "Diodes Incorporated")
        (field (name "MPN") "S1M-13-F")
      )
      (libsource (lib "eagle-import") (part "DIODE-DO214AC"))
    )
    (comp (ref "D15")
      (value "1000Vr")
      (footprint "eagle-import:DO214AC")
      (description "DIODE GEN PURP 1KV 1A SMA")
      (fields
        (field (name "DIGIKEY") "S1M-FDICT-ND")
        (field (name "MANUFACTURER") "Diodes Incorporated")
        (field (name "MPN") "S1M-13-F")
      )
      (libsource (lib "eagle-import") (part "DIODE-DO214AC"))
    )
    (comp (ref "F1")
      (value "300VAC - 500ma")
      (footprint "eagle-import:MIRCRO_FUSE_5MM")
      (description "FUSE BRD MNT 500MA 350VAC 100VDC")
      (fields (field (name "MANUFACTURER") "Bel Fuse Inc") (field (name "MPN") "0697H0500-01"))
      (libsource (lib "eagle-import") (part "MICRO_FUSE500MA_350VAC"))
    )
    (comp (ref "R1")
      (value "1")
      (footprint "eagle-import:R2512")
      (description "RES SMD 1 OHM 5% 2W 2512")
      (fields
        (field (name "DIGIKEY") "CRM2512-JW-1R0ELFCT-ND")
        (field (name "MANUFACTURER") "Bourns Inc.")
        (field (name "MPN") "CRM2512-JW-1R0ELF")
      )
      (libsource (lib "eagle-import") (part "R-US_R2512"))
    )
    (comp (ref "R2")
      (value "10")
      (footprint "eagle-import:0402_RES")
      (description "RES SMD 10 OHM 1% 1/16W 0402")
      (fields (field (name "MANUFACTURER") "Yageo") (field (name "MPN") "RC0402FR-0710RL"))
      (libsource (lib "eagle-import") (part "RESISTOR0402_RES"))
    )
    (comp (ref "R3")
      (value "10")
      (footprint "eagle-import:0402_RES")
      (description "RES SMD 10 OHM 1% 1/16W 0402")
      (fields (field (name "MANUFACTURER") "Yageo") (field (name "MPN") "RC0402FR-0710RL"))
      (libsource (lib "eagle-import") (part "RESISTOR0402_RES"))
    )
    (comp (ref "R6")
      (value "1.00k")
      (footprint "eagle-import:0402_RES")
      (description "RES SMD 1K OHM 0.1% 1/16W 0402")
      (fields (field (name "MANUFACTURER") "Yageo") (field (name "MPN") "RT0402BRE071KL"))
      (libsource (lib "eagle-import") (part "RESISTOR0402_RES"))
    )
    (comp (ref "R7")
      (value "1.00k")
      (footprint "eagle-import:0402_RES")
      (description "RES SMD 1K OHM 0.1% 1/16W 0402")
      (fields (field (name "MANUFACTURER") "Yageo") (field (name "MPN") "RT0402BRE071KL"))
      (libsource (lib "eagle-import") (part "RESISTOR0402_RES"))
    )
    (comp (ref "R10")
      (value "3.74k")
      (footprint "eagle-import:0402_RES")
      (description "RES SMD 3.74KOHM 0.1% 1/16W 0402")
      (fields
        (field (name "MANUFACTURER") "Panasonic Electronic Components")
        (field (name "MPN") "ERA-2AEB3741X")
      )
      (libsource (lib "eagle-import") (part "RESISTOR0402_RES"))
    )
    (comp (ref "R11")
      (value "3.74k")
      (footprint "eagle-import:0402_RES")
      (description "RES SMD 3.74KOHM 0.1% 1/16W 0402")
      (fields
        (field (name "MANUFACTURER") "Panasonic Electronic Components")
        (field (name "MPN") "ERA-2AEB3741X")
      )
      (libsource (lib "eagle-import") (part "RESISTOR0402_RES"))
    )
    (comp (ref "R31")
      (value "100k")
      (footprint "eagle-import:0402_RES")
      (description "RES SMD 100K OHM 1% 1/16W 0402")
      (fields (field (name "MANUFACTURER") "Yageo") (field (name "MPN") "RC0402FR-07100KL"))
      (libsource (lib "eagle-import") (part "RESISTOR0402_RES"))
    )
    (comp (ref "R34")
      (value "953k")
      (footprint "eagle-import:0805_RES")
      (description "RES SMD 953K OHM 0.1% 1/8W 0805")
      (fields
        (field (name "MANUFACTURER") "Panasonic Electronic Components")
        (field (name "MPN") "ERA-6AEB9533V")
      )
      (libsource (lib "eagle-import") (part "RESISTOR0805_RES"))
    )
    (comp (ref "R35")
      (value "953k")
      (footprint "eagle-import:0805_RES")
      (description "RES SMD 953K OHM 0.1% 1/8W 0805")
      (fields
        (field (name "MANUFACTURER") "Panasonic Electronic Components")
        (field (name "MPN") "ERA-6AEB9533V")
      )
      (libsource (lib "eagle-import") (part "RESISTOR0805_RES"))
    )
    (comp (ref "R36")
      (value "953k")
      (footprint "eagle-import:0805_RES")
      (description "RES SMD 953K OHM 0.1% 1/8W 0805")
      (fields
        (field (name "MANUFACTURER") "Panasonic Electronic Components")
        (field (name "MPN") "ERA-6AEB9533V")
      )
      (libsource (lib "eagle-import") (part "RESISTOR0805_RES"))
    )
    (comp (ref "R37")
      (value "953k")
      (footprint "eagle-import:0805_RES")
      (description "RES SMD 953K OHM 0.1% 1/8W 0805")
      (fields
        (field (name "MANUFACTURER") "Panasonic Electronic Components")
        (field (name "MPN") "ERA-6AEB9533V")
      )
      (libsource (lib "eagle-import") (part "RESISTOR0805_RES"))
    )
    (comp (ref "R38")
      (value "953k")
      (footprint "eagle-import:0805_RES")
      (description "RES SMD 953K OHM 0.1% 1/8W 0805")
      (fields
        (field (name "MANUFACTURER") "Panasonic Electronic Components")
        (field (name "MPN") "ERA-6AEB9533V")
      )
      (libsource (lib "eagle-import") (part "RESISTOR0805_RES"))
    )
    (comp (ref "R39")
      (value "953k")
      (footprint "eagle-import:0805_RES")
      (description "RES SMD 953K OHM 0.1% 1/8W 0805")
      (fields
        (field (name "MANUFACTURER") "Panasonic Electronic Components")
        (field (name "MPN") "ERA-6AEB9533V")
      )
      (libsource (lib "eagle-import") (part "RESISTOR0805_RES"))
    )
    (comp (ref "R40")
      (value "953k")
      (footprint "eagle-import:0805_RES")
      (description "RES SMD 953K OHM 0.1% 1/8W 0805")
      (fields
        (field (name "MANUFACTURER") "Panasonic Electronic Components")
        (field (name "MPN") "ERA-6AEB9533V")
      )
      (libsource (lib "eagle-import") (part "RESISTOR0805_RES"))
    )
    (comp (ref "R41")
      (value "953k")
      (footprint "eagle-import:0805_RES")
      (description "RES SMD 953K OHM 0.1% 1/8W 0805")
      (fields
        (field (name "MANUFACTURER") "Panasonic Electronic Components")
        (field (name "MPN") "ERA-6AEB9533V")
      )
      (libsource (lib "eagle-import") (part "RESISTOR0805_RES"))
    )
    (comp (ref "TP3")
      (value "TEST_POINT_0.060IN")
      (footprint "eagle-import:TESTPOINT_0.060IN")
      (libsource (lib "eagle-import") (part "TEST_POINT_0.060IN"))
    )
    (comp (ref "TP4")
      (value "TEST_POINT_0.060IN")
      (footprint "eagle-import:TESTPOINT_0.060IN")
      (libsource (lib "eagle-import") (part "TEST_POINT_0.060IN"))
    )
    (comp (ref "U2")
      (value "ADA4096-4ACPZ-R7")
      (footprint "eagle-import:CP_16_27")
      (description "IC OPAMP GP 4 CIRCUIT 16LFCSP")
      (fields
        (field (name "MANUFACTURER_PART_NUMBER") "ADA40964ACPZR7")
        (field (name "DIGIKEY") "ADA4096-4ACPZ-R7CT-ND")
        (field (name "MANUFACTURER") "Analog Devices Inc.")
        (field (name "MPN") "ADA4096-4ACPZ-R7")
      )
      (libsource (lib "eagle-import") (part "ADA4096-4ACPZ-R7"))
    )
    (comp (ref "U6")
      (value "IRM-03-5V")
      (footprint "eagle-import:IRM-03")
      (fields (field (name "MANUFACTURER") "Mean Well USA") (field (name "MPN") "IRM-03-5"))
      (libsource (lib "eagle-import") (part "IRM-03-5V"))
    )
    (comp (ref "U11")
      (value "REF2030AIDDCR")
      (footprint "eagle-import:DDC5")
      (description "IC VREF SERIES 1.5V/3V 5SOT")
      (fields
        (field (name "MANUFACTURER_PART_NUMBER") "REF2033AIDDCR")
        (field (name "DIGIKEY") "296-47351-1-ND")
        (field (name "MANUFACTURER") "Texas Instruments")
        (field (name "MANUFACTURER_PART_NUMBER_1") "REF2030AIDDCR")
        (field (name "MPN") "REF2030AIDDCR")
      )
      (libsource (lib "eagle-import") (part "REF2033AIDDCR"))
    )
    (comp (ref "U14")
      (value "SIP32510")
      (footprint "eagle-import:TSOT23-6")
      (fields (field (name "MANUFACTURER") "Vishay") (field (name "MPN") "SIP32510DT-T1-GE3"))
      (libsource (lib "eagle-import") (part "SIP32510"))
    )
    (comp (ref "V1")
      (value "S14K385")
      (footprint "eagle-import:S14K385")
      (description "VARISTOR 620V 5KA DISC 14MM")
      (fields (field (name "MANUFACTURER") "EPCOS (TDK)") (field (name "MPN") "B72214S2381K101"))
      (libsource (lib "eagle-import") (part "S14K385"))
    )
    (comp (ref "C9")
      (value "0.1uF")
      (footprint "eagle-import:0402_CAP")
      (description "CAP CER 0.1UF 10V X5R 0402")
      (fields (field (name "MANUFACTURER") "Yageo") (field (name "MPN") "CC0402KRX5R6BB104"))
      (libsource (lib "eagle-import") (part "CAPACITOR0402_CAP"))
    )
    (comp (ref "C25")
      (value "10uF")
      (footprint "eagle-import:0402_CAP")
      (description "CAP CER 10UF 6.3V X5R 0402")
      (fields
        (field (name "MANUFACTURER") "Murata Electronics North America")
        (field (name "MPN") "GRJ155R60J106ME11D")
      )
      (libsource (lib "eagle-import") (part "CAPACITOR0402_CAP"))
    )
    (comp (ref "R13")
      (value "10k")
      (footprint "eagle-import:0402_RES")
      (description "RES SMD 10K OHM 1% 1/16W 0402")
      (fields
        (field (name "MANUFACTURER") "Stackpole Electronics Inc. ")
        (field (name "MPN") "RMCF0402FT10K0 ")
      )
      (libsource (lib "eagle-import") (part "RESISTOR0402_RES"))
    )
    (comp (ref "R17")
      (value "10k")
      (footprint "eagle-import:0402_RES")
      (description "RES SMD 10K OHM 1% 1/16W 0402")
      (fields
        (field (name "MANUFACTURER") "Stackpole Electronics Inc. ")
        (field (name "MPN") "RMCF0402FT10K0 ")
      )
      (libsource (lib "eagle-import") (part "RESISTOR0402_RES"))
    )
    (comp (ref "U7")
      (value "LIS2DH12")
      (footprint "eagle-import:LGA-12")
      (fields
        (field (name "MANUFACTURER") "STMicroelectronics")
        (field (name "MPN") "LIS2DW12TR")
        (field (name "DIGIKEY") "497-14851-1-ND")
        (field (name "MOUSER") "511-LIS2DH12TR")
        (field (name "MPN_1") "LIS2DH12TR")
      )
      (libsource (lib "eagle-import") (part "LIS2DW12"))
    )
    (comp (ref "A1")
      (value "GPS-ANTENNA")
      (footprint "eagle-import:ANT1818B00BT1516S")
      (description "PATCH ANT GPS/GLO CP SMD")
      (fields (field (name "MANUFACTURER") "Yageo") (field (name "MPN") "ANT1818B00BT1516S"))
      (libsource (lib "eagle-import") (part "GPS-ANTENNA"))
    )
    (comp (ref "C4")
      (value "10nF")
      (footprint "eagle-import:0402_CAP")
      (description "CAP CER 10000PF 16V X7R 0402")
      (fields
        (field (name "MANUFACTURER") "Murata Electronics North America")
        (field (name "MPN") "GRM155R71C103KA01D")
      )
      (libsource (lib "eagle-import") (part "CAPACITOR0402_CAP"))
    )
    (comp (ref "C5")
      (value "10nF")
      (footprint "eagle-import:0402_CAP")
      (description "CAP CER 10000PF 16V X7R 0402")
      (fields
        (field (name "MANUFACTURER") "Murata Electronics North America")
        (field (name "MPN") "GRM155R71C103KA01D")
      )
      (libsource (lib "eagle-import") (part "CAPACITOR0402_CAP"))
    )
    (comp (ref "C8")
      (value "0.1uF")
      (footprint "eagle-import:0402_CAP")
      (description "CAP CER 0.1UF 10V X5R 0402")
      (fields (field (name "MANUFACTURER") "Yageo") (field (name "MPN") "CC0402KRX5R6BB104"))
      (libsource (lib "eagle-import") (part "CAPACITOR0402_CAP"))
    )
    (comp (ref "C26")
      (value "10uF")
      (footprint "eagle-import:0402_CAP")
      (description "CAP CER 10UF 6.3V X5R 0402")
      (fields
        (field (name "MANUFACTURER") "Murata Electronics North America")
        (field (name "MPN") "GRJ155R60J106ME11D")
      )
      (libsource (lib "eagle-import") (part "CAPACITOR0402_CAP"))
    )
    (comp (ref "L1")
      (value "5.6n")
      (footprint "eagle-import:0402_CAP")
      (description "FIXED IND 5.6NH 1.77A 40 MOHM")
      (fields (field (name "MANUFACTURER") "Murata") (field (name "MPN") "LQW15AN5N6B80D"))
      (libsource (lib "eagle-import") (part "INDUCTOR0402"))
    )
    (comp (ref "L2")
      (value "1k")
      (footprint "eagle-import:0402_CAP")
      (description "FERRITE BEAD 1 KOHM 0402 1LN")
      (fields (field (name "MANUFACTURER") "Murata") (field (name "MPN") "BLM15HD102SN1D"))
      (libsource (lib "eagle-import") (part "FERRITE_BEAD0402"))
    )
    (comp (ref "L3")
      (value "1k")
      (footprint "eagle-import:0402_CAP")
      (description "FERRITE BEAD 1 KOHM 0402 1LN")
      (fields (field (name "MANUFACTURER") "Murata") (field (name "MPN") "BLM15HD102SN1D"))
      (libsource (lib "eagle-import") (part "FERRITE_BEAD0402"))
    )
    (comp (ref "R28")
      (value "100k")
      (footprint "eagle-import:0402_RES")
      (description "RES SMD 100K OHM 1% 1/16W 0402")
      (fields (field (name "MANUFACTURER") "Yageo") (field (name "MPN") "RC0402FR-07100KL"))
      (libsource (lib "eagle-import") (part "RESISTOR0402_RES"))
    )
    (comp (ref "U3")
      (value "BGA725L6-ALT")
      (footprint "eagle-import:LNA-TSLP-6-2-ALT")
      (description "IC AMP MMIC RF LNA 20DB TSLP-6")
      (fields (field (name "MANUFACTURER") "Infineon") (field (name "MPN") "BGA725L6E6327FTSA1"))
      (libsource (lib "eagle-import") (part "BGA725L6-ALT"))
    )
    (comp (ref "U5")
      (value "SAFFB1G56KB0F0A")
      (footprint "eagle-import:QCS5I")
      (description "FILTER SAW 1.575GHZ 5SMD")
      (fields (field (name "MANUFACTURER") "Taiyo Yuden") (field (name "MPN") "F6QA1G575H2JF-J"))
      (libsource (lib "eagle-import") (part "FILTERS"))
    )
    (comp (ref "U8")
      (value "MAX-M8")
      (footprint "eagle-import:MAX-M8")
      (description "IC RECEIVER GPS/GNSS 18LCC")
      (fields (field (name "MANUFACTURER") "u-blox") (field (name "MPN") "MAX-M8Q-0"))
      (libsource (lib "eagle-import") (part "MAX-M8"))
    )
    (comp (ref "U12")
      (value "SIP32510")
      (footprint "eagle-import:TSOT23-6")
      (fields (field (name "MANUFACTURER") "Vishay") (field (name "MPN") "SIP32510DT-T1-GE3"))
      (libsource (lib "eagle-import") (part "SIP32510"))
    )
  )
  (nets
    (net (code "1") (name "5V") (class "Default")
      (node (ref "ASSY1") (pin "VIN") (pinfunction "VIN_VIN") (pintype "power_in"))
      (node (ref "C27") (pin "1") (pinfunction "1_1") (pintype "bidirectional"))
      (node (ref "C28") (pin "1") (pinfunction "1_1") (pintype "bidirectional"))
      (node (ref "C29") (pin "+") (pinfunction "+_+") (pintype "passive"))
      (node (ref "R24") (pin "1") (pinfunction "1_1") (pintype "passive"))
      (node (ref "R29") (pin "1") (pinfunction "1_1") (pintype "passive"))
      (node (ref "R43") (pin "1") (pinfunction "1_1") (pintype "passive"))
      (node (ref "U6") (pin "V+") (pinfunction "V+_V+") (pintype "bidirectional"))
    )
    (net (code "2") (name "ACCEL_INT") (class "Default")
      (node (ref "ASSY1") (pin "C4") (pinfunction "C4_C4") (pintype "bidirectional"))
      (node (ref "U7") (pin "12") (pinfunction "INT1_12") (pintype "bidirectional"))
    )
    (net (code "3") (name "AC_COPROC_VCC") (class "Default")
      (node (ref "C15") (pin "1") (pinfunction "1_1") (pintype "bidirectional"))
      (node (ref "C16") (pin "1") (pinfunction "1_1") (pintype "bidirectional"))
      (node (ref "C20") (pin "1") (pinfunction "1_1") (pintype "bidirectional"))
      (node (ref "C21") (pin "1") (pinfunction "1_1") (pintype "bidirectional"))
      (node (ref "C24") (pin "1") (pinfunction "1_1") (pintype "bidirectional"))
      (node (ref "J2") (pin "1") (pinfunction "VCC_1") (pintype "bidirectional"))
      (node (ref "R9") (pin "2") (pinfunction "2_2") (pintype "passive"))
      (node (ref "U15") (pin "1") (pinfunction "VDD_1") (pintype "bidirectional"))
      (node (ref "U15") (pin "17") (pinfunction "VDD_17") (pintype "bidirectional"))
      (node (ref "U16") (pin "3") (pinfunction "VCCA_3") (pintype "power_in"))
      (node (ref "U16") (pin "6") (pinfunction "OE_6") (pintype "input"))
      (node (ref "U17") (pin "5") (pinfunction "OUT_5") (pintype "output"))
    )
    (net (code "4") (name "AC_L_800V_DETECT") (class "Default")
      (node (ref "ASSY1") (pin "B1") (pinfunction "B1_B1") (pintype "bidirectional"))
      (node (ref "C6") (pin "1") (pinfunction "1_1") (pintype "bidirectional"))
      (node (ref "D1") (pin "C") (pinfunction "C_C") (pintype "passive"))
      (node (ref "D6") (pin "A") (pinfunction "A_A") (pintype "passive"))
      (node (ref "U15") (pin "27") (pinfunction "PB4/~{JTRST}_27") (pintype "bidirectional"))
    )
    (net (code "5") (name "AC_L_HV_OUT") (class "Default")
      (node (ref "ASSY1") (pin "A0") (pinfunction "A0_A0") (pintype "bidirectional"))
      (node (ref "R6") (pin "2") (pinfunction "2_2") (pintype "passive"))
      (node (ref "U15") (pin "6") (pinfunction "PA0/CLKIN_6") (pintype "bidirectional"))
      (node (ref "U2") (pin "14") (pinfunction "OUT_14") (pintype "bidirectional"))
    )
    (net (code "6") (name "AC_L_LV_OUT") (class "Default")
      (node (ref "ASSY1") (pin "B3") (pinfunction "B3_B3") (pintype "bidirectional"))
      (node (ref "R10") (pin "2") (pinfunction "2_2") (pintype "passive"))
      (node (ref "U15") (pin "9") (pinfunction "PA3_9") (pintype "bidirectional"))
      (node (ref "U2") (pin "7") (pinfunction "OUT_7") (pintype "bidirectional"))
    )
    (net (code "7") (name "AC_L_SENSE") (class "Default")
      (node (ref "D14") (pin "A") (pinfunction "A_A") (pintype "passive"))
      (node (ref "F1") (pin "P$2") (pinfunction "P$2_P$2") (pintype "bidirectional"))
      (node (ref "R1") (pin "1") (pinfunction "1_1") (pintype "passive"))
      (node (ref "R34") (pin "1") (pinfunction "1_1") (pintype "passive"))
      (node (ref "R39") (pin "2") (pinfunction "2_2") (pintype "passive"))
    )
    (net (code "8") (name "AC_N") (class "Default")
      (node (ref "D15") (pin "A") (pinfunction "A_A") (pintype "passive"))
      (node (ref "R36") (pin "1") (pinfunction "1_1") (pintype "passive"))
      (node (ref "R40") (pin "2") (pinfunction "2_2") (pintype "passive"))
      (node (ref "TP4") (pin "TESTPOINT") (pinfunction "TESTPOINT_TESTPOINT") (pintype "bidirectional"))
      (node (ref "U6") (pin "AC/N") (pinfunction "AC/N_AC/N") (pintype "bidirectional"))
      (node (ref "V1") (pin "2") (pinfunction "2_2") (pintype "passive"))
    )
    (net (code "9") (name "AC_N_800V_DETECT") (class "Default")
      (node (ref "ASSY1") (pin "A1") (pinfunction "A1_A1") (pintype "bidirectional"))
      (node (ref "C7") (pin "1") (pinfunction "1_1") (pintype "bidirectional"))
      (node (ref "D10") (pin "A") (pinfunction "A_A") (pintype "passive"))
      (node (ref "D2") (pin "C") (pinfunction "C_C") (pintype "passive"))
      (node (ref "U15") (pin "28") (pinfunction "PB5_28") (pintype "bidirectional"))
    )
    (net (code "10") (name "AC_N_HV_OUT") (class "Default")
      (node (ref "ASSY1") (pin "B4") (pinfunction "B4_B4") (pintype "bidirectional"))
      (node (ref "R7") (pin "2") (pinfunction "2_2") (pintype "passive"))
      (node (ref "U15") (pin "10") (pinfunction "PA4_10") (pintype "bidirectional"))
      (node (ref "U2") (pin "6") (pinfunction "OUT_6") (pintype "bidirectional"))
    )
    (net (code "11") (name "AC_N_LV_OUT") (class "Default")
      (node (ref "ASSY1") (pin "B5") (pinfunction "B5_B5") (pintype "bidirectional"))
      (node (ref "R11") (pin "1") (pinfunction "1_1") (pintype "passive"))
      (node (ref "U15") (pin "7") (pinfunction "PA1_7") (pintype "bidirectional"))
      (node (ref "U2") (pin "15") (pinfunction "OUT_15") (pintype "bidirectional"))
    )
    (net (code "12") (name "AC_SCL") (class "Default")
      (node (ref "U15") (pin "19") (pinfunction "PA9_19") (pintype "bidirectional"))
      (node (ref "U16") (pin "5") (pinfunction "SCL_A_5") (pintype "bidirectional"))
    )
    (net (code "13") (name "AC_SDA") (class "Default")
      (node (ref "U15") (pin "20") (pinfunction "PA10_20") (pintype "bidirectional"))
      (node (ref "U16") (pin "4") (pinfunction "SDA_A_4") (pintype "bidirectional"))
    )
    (net (code "14") (name "AC_SENSE_PWR_EN") (class "Default")
      (node (ref "ASSY1") (pin "C3") (pinfunction "C3_C3") (pintype "bidirectional"))
      (node (ref "R31") (pin "2") (pinfunction "2_2") (pintype "passive"))
      (node (ref "U14") (pin "3") (pinfunction "EN_3") (pintype "bidirectional"))
    )
    (net (code "15") (name "AC_SENSE_VCC") (class "Default")
      (node (ref "U11") (pin "3") (pinfunction "EN_3") (pintype "input"))
      (node (ref "U11") (pin "4") (pinfunction "VIN_4") (pintype "input"))
      (node (ref "U14") (pin "1") (pinfunction "VLOAD_1") (pintype "bidirectional"))
      (node (ref "U14") (pin "2") (pinfunction "VLOAD_2") (pintype "bidirectional"))
      (node (ref "U17") (pin "1") (pinfunction "IN_1") (pintype "input"))
      (node (ref "U17") (pin "3") (pinfunction "EN_3") (pintype "passive"))
    )
    (net (code "16") (name "ANT") (class "Default")
      (node (ref "A1") (pin "0") (pinfunction "1_0") (pintype "output"))
      (node (ref "L1") (pin "2") (pinfunction "2_2") (pintype "bidirectional"))
    )
    (net (code "17") (name "BOOT0") (class "Default")
      (node (ref "R23") (pin "2") (pinfunction "2_2") (pintype "passive"))
      (node (ref "U15") (pin "31") (pinfunction "PH3/BOOT0_31") (pintype "bidirectional"))
    )
    (net (code "18") (name "DO_NOT_CONNECT") (class "Default")
      (node (ref "ASSY1") (pin "D7") (pinfunction "D7_D7") (pintype "bidirectional"))
    )
    (net (code "19") (name "GND") (class "Default")
      (node (ref "A1") (pin "1") (pinfunction "2_1") (pintype "power_in"))
      (node (ref "A1") (pin "2") (pinfunction "2_2") (pintype "power_in"))
      (node (ref "A1") (pin "3") (pinfunction "2_3") (pintype "power_in"))
      (node (ref "A1") (pin "4") (pinfunction "2_4") (pintype "power_in"))
      (node (ref "ASSY1") (pin "GND") (pinfunction "GND_GND") (pintype "power_in"))
      (node (ref "ASSY1") (pin "GND@2") (pinfunction "GND_GND@2") (pintype "power_in"))
      (node (ref "B1") (pin "-") (pinfunction "-_-") (pintype "bidirectional"))
      (node (ref "C1") (pin "1") (pinfunction "1_1") (pintype "bidirectional"))
      (node (ref "C10") (pin "2") (pinfunction "2_2") (pintype "bidirectional"))
      (node (ref "C11") (pin "2") (pinfunction "2_2") (pintype "bidirectional"))
      (node (ref "C12") (pin "2") (pinfunction "2_2") (pintype "bidirectional"))
      (node (ref "C13") (pin "2") (pinfunction "2_2") (pintype "bidirectional"))
      (node (ref "C14") (pin "2") (pinfunction "2_2") (pintype "bidirectional"))
      (node (ref "C15") (pin "2") (pinfunction "2_2") (pintype "bidirectional"))
      (node (ref "C16") (pin "2") (pinfunction "2_2") (pintype "bidirectional"))
      (node (ref "C17") (pin "2") (pinfunction "2_2") (pintype "bidirectional"))
      (node (ref "C18") (pin "2") (pinfunction "2_2") (pintype "bidirectional"))
      (node (ref "C19") (pin "2") (pinfunction "2_2") (pintype "bidirectional"))
      (node (ref "C2") (pin "1") (pinfunction "1_1") (pintype "bidirectional"))
      (node (ref "C20") (pin "2") (pinfunction "2_2") (pintype "bidirectional"))
      (node (ref "C21") (pin "2") (pinfunction "2_2") (pintype "bidirectional"))
      (node (ref "C22") (pin "2") (pinfunction "2_2") (pintype "bidirectional"))
      (node (ref "C23") (pin "2") (pinfunction "2_2") (pintype "bidirectional"))
      (node (ref "C24") (pin "2") (pinfunction "2_2") (pintype "bidirectional"))
      (node (ref "C25") (pin "2") (pinfunction "2_2") (pintype "bidirectional"))
      (node (ref "C26") (pin "1") (pinfunction "1_1") (pintype "bidirectional"))
      (node (ref "C27") (pin "2") (pinfunction "2_2") (pintype "bidirectional"))
      (node (ref "C28") (pin "2") (pinfunction "2_2") (pintype "bidirectional"))
      (node (ref "C29") (pin "-") (pinfunction "-_-") (pintype "passive"))
      (node (ref "C3") (pin "2") (pinfunction "2_2") (pintype "bidirectional"))
      (node (ref "C4") (pin "1") (pinfunction "1_1") (pintype "bidirectional"))
      (node (ref "C5") (pin "1") (pinfunction "1_1") (pintype "bidirectional"))
      (node (ref "C6") (pin "2") (pinfunction "2_2") (pintype "bidirectional"))
      (node (ref "C7") (pin "2") (pinfunction "2_2") (pintype "bidirectional"))
      (node (ref "C8") (pin "1") (pinfunction "1_1") (pintype "bidirectional"))
      (node (ref "C9") (pin "2") (pinfunction "2_2") (pintype "bidirectional"))
      (node (ref "D1") (pin "A") (pinfunction "A_A") (pintype "passive"))
      (node (ref "D2") (pin "A") (pinfunction "A_A") (pintype "passive"))
      (node (ref "J1") (pin "6") (pinfunction "GND_6") (pintype "bidirectional"))
      (node (ref "J1") (pin "B") (pinfunction "B_B") (pintype "bidirectional"))
      (node (ref "J1") (pin "MOUNT0") (pinfunction "GND_MOUNT0") (pintype "bidirectional"))
      (node (ref "J1") (pin "MOUNT1") (pinfunction "GND_MOUNT1") (pintype "bidirectional"))
      (node (ref "J1") (pin "MOUNT2") (pinfunction "GND_MOUNT2") (pintype "bidirectional"))
      (node (ref "J1") (pin "MOUNT3") (pinfunction "GND_MOUNT3") (pintype "bidirectional"))
      (node (ref "J2") (pin "5") (pinfunction "GND_5") (pintype "bidirectional"))
      (node (ref "JP1") (pin "GND") (pinfunction "1_GND") (pintype "passive"))
      (node (ref "JP2") (pin "GND") (pinfunction "1_GND") (pintype "passive"))
      (node (ref "Q1") (pin "2") (pinfunction "S_2") (pintype "passive"))
      (node (ref "R18") (pin "2") (pinfunction "2_2") (pintype "passive"))
      (node (ref "R23") (pin "1") (pinfunction "1_1") (pintype "passive"))
      (node (ref "R25") (pin "2") (pinfunction "2_2") (pintype "passive"))
      (node (ref "R27") (pin "1") (pinfunction "1_1") (pintype "passive"))
      (node (ref "R28") (pin "1") (pinfunction "1_1") (pintype "passive"))
      (node (ref "R30") (pin "2") (pinfunction "2_2") (pintype "passive"))
      (node (ref "R31") (pin "1") (pinfunction "1_1") (pintype "passive"))
      (node (ref "R35") (pin "1") (pinfunction "1_1") (pintype "passive"))
      (node (ref "R37") (pin "1") (pinfunction "1_1") (pintype "passive"))
      (node (ref "R38") (pin "2") (pinfunction "2_2") (pintype "passive"))
      (node (ref "R41") (pin "2") (pinfunction "2_2") (pintype "passive"))
      (node (ref "R42") (pin "2") (pinfunction "2_2") (pintype "passive"))
      (node (ref "R44") (pin "2") (pinfunction "2_2") (pintype "passive"))
      (node (ref "S1") (pin "1") (pinfunction "P$1_1") (pintype "passive"))
      (node (ref "U1") (pin "3") (pinfunction "~{EXTR}_3") (pintype "bidirectional"))
      (node (ref "U1") (pin "GND") (pinfunction "VSS_GND") (pintype "bidirectional"))
      (node (ref "U10") (pin "17") (pinfunction "EPAD_17") (pintype "power_in"))
      (node (ref "U10") (pin "6") (pinfunction "GND_6") (pintype "power_in"))
      (node (ref "U11") (pin "2") (pinfunction "GND_2") (pintype "power_in"))
      (node (ref "U12") (pin "4") (pinfunction "GND_4") (pintype "bidirectional"))
      (node (ref "U13") (pin "4") (pinfunction "GND_4") (pintype "bidirectional"))
      (node (ref "U14") (pin "4") (pinfunction "GND_4") (pintype "bidirectional"))
      (node (ref "U15") (pin "16") (pinfunction "VSS_16") (pintype "bidirectional"))
      (node (ref "U15") (pin "32") (pinfunction "VSS_32") (pintype "bidirectional"))
      (node (ref "U15") (pin "THERMAL") (pinfunction "VSS_THERMAL") (pintype "bidirectional"))
      (node (ref "U16") (pin "2") (pinfunction "GND_2") (pintype "power_in"))
      (node (ref "U17") (pin "2") (pinfunction "GND_2") (pintype "power_in"))
      (node (ref "U2") (pin "10") (pinfunction "V-_10") (pintype "bidirectional"))
      (node (ref "U2") (pin "17") (pinfunction "V-_17") (pintype "bidirectional"))
      (node (ref "U3") (pin "1") (pinfunction "GND_1") (pintype "power_in"))
      (node (ref "U3") (pin "4") (pinfunction "GND_4") (pintype "power_in"))
      (node (ref "U4") (pin "1") (pinfunction "GND_1") (pintype "power_in"))
      (node (ref "U5") (pin "2") (pinfunction "GND_2") (pintype "power_in"))
      (node (ref "U5") (pin "3") (pinfunction "GND_3") (pintype "power_in"))
      (node (ref "U5") (pin "5") (pinfunction "GND_5") (pintype "power_in"))
      (node (ref "U6") (pin "V-") (pinfunction "V-_V-") (pintype "bidirectional"))
      (node (ref "U7") (pin "3") (pinfunction "MISO/SA0_3") (pintype "bidirectional"))
      (node (ref "U7") (pin "5") (pinfunction "GND_5") (pintype "bidirectional"))
      (node (ref "U7") (pin "6") (pinfunction "GND_6") (pintype "bidirectional"))
      (node (ref "U7") (pin "7") (pinfunction "GND_7") (pintype "bidirectional"))
      (node (ref "U7") (pin "8") (pinfunction "GND_8") (pintype "bidirectional"))
      (node (ref "U8") (pin "1") (pinfunction "GND_1") (pintype "bidirectional"))
      (node (ref "U8") (pin "10") (pinfunction "GND_10") (pintype "bidirectional"))
      (node (ref "U8") (pin "12") (pinfunction "GND_12") (pintype "bidirectional"))
      (node (ref "U9") (pin "4") (pinfunction "GND_4") (pintype "bidirectional"))
    )
    (net (code "20") (name "GPS_PPS") (class "Default")
      (node (ref "ASSY1") (pin "D4") (pinfunction "D4_D4") (pintype "bidirectional"))
      (node (ref "U15") (pin "26") (pinfunction "PB3/JTDO/SWO_26") (pintype "bidirectional"))
      (node (ref "U8") (pin "4") (pinfunction "TIMEPULSE_4") (pintype "bidirectional"))
    )
    (net (code "21") (name "GPS_PWR_EN") (class "Default")
      (node (ref "ASSY1") (pin "B2") (pinfunction "B2_B2") (pintype "bidirectional"))
      (node (ref "R28") (pin "2") (pinfunction "2_2") (pintype "passive"))
      (node (ref "U12") (pin "3") (pinfunction "EN_3") (pintype "bidirectional"))
    )
    (net (code "22") (name "GPS_RXD") (class "Default")
      (node (ref "ASSY1") (pin "TX") (pinfunction "TX_TX") (pintype "bidirectional"))
      (node (ref "L3") (pin "2") (pinfunction "P$2_2") (pintype "bidirectional"))
    )
    (net (code "23") (name "GPS_TXD") (class "Default")
      (node (ref "ASSY1") (pin "RX") (pinfunction "RX_RX") (pintype "bidirectional"))
      (node (ref "L2") (pin "2") (pinfunction "P$2_2") (pintype "bidirectional"))
    )
    (net (code "24") (name "GPS_VCC") (class "Default")
      (node (ref "C26") (pin "2") (pinfunction "2_2") (pintype "bidirectional"))
      (node (ref "C5") (pin "2") (pinfunction "2_2") (pintype "bidirectional"))
      (node (ref "C8") (pin "2") (pinfunction "2_2") (pintype "bidirectional"))
      (node (ref "U12") (pin "1") (pinfunction "VLOAD_1") (pintype "bidirectional"))
      (node (ref "U12") (pin "2") (pinfunction "VLOAD_2") (pintype "bidirectional"))
      (node (ref "U8") (pin "6") (pinfunction "V_BCKP_6") (pintype "bidirectional"))
      (node (ref "U8") (pin "7") (pinfunction "VCC_IO_7") (pintype "bidirectional"))
      (node (ref "U8") (pin "8") (pinfunction "VCC_8") (pintype "bidirectional"))
    )
    (net (code "25") (name "Net-(D5-ANODE)") (class "Default")
      (node (ref "D5") (pin "A") (pinfunction "ANODE_A") (pintype "bidirectional"))
      (node (ref "R9") (pin "1") (pinfunction "1_1") (pintype "passive"))
    )
    (net (code "26") (name "Net-(D5-CATHODE)") (class "Default")
      (node (ref "D5") (pin "C") (pinfunction "CATHODE_C") (pintype "bidirectional"))
      (node (ref "U15") (pin "15") (pinfunction "PB1_15") (pintype "bidirectional"))
    )
    (net (code "27") (name "Net-(D6-PadC)") (class "Default")
      (node (ref "D6") (pin "C") (pinfunction "C_C") (pintype "passive"))
      (node (ref "D7") (pin "A") (pinfunction "A_A") (pintype "passive"))
    )
    (net (code "28") (name "Net-(D7-PadC)") (class "Default")
      (node (ref "D7") (pin "C") (pinfunction "C_C") (pintype "passive"))
      (node (ref "D8") (pin "A") (pinfunction "A_A") (pintype "passive"))
    )
    (net (code "29") (name "Net-(D8-PadC)") (class "Default")
      (node (ref "D8") (pin "C") (pinfunction "C_C") (pintype "passive"))
      (node (ref "D9") (pin "A") (pinfunction "A_A") (pintype "passive"))
    )
    (net (code "30") (name "Net-(D9-PadC)") (class "Default")
      (node (ref "D9") (pin "C") (pinfunction "C_C") (pintype "passive"))
      (node (ref "R2") (pin "1") (pinfunction "1_1") (pintype "passive"))
    )
    (net (code "31") (name "Net-(D10-PadC)") (class "Default")
      (node (ref "D10") (pin "C") (pinfunction "C_C") (pintype "passive"))
      (node (ref "D11") (pin "A") (pinfunction "A_A") (pintype "passive"))
    )
    (net (code "32") (name "Net-(D11-PadC)") (class "Default")
      (node (ref "D11") (pin "C") (pinfunction "C_C") (pintype "passive"))
      (node (ref "D12") (pin "A") (pinfunction "A_A") (pintype "passive"))
    )
    (net (code "33") (name "Net-(D12-PadC)") (class "Default")
      (node (ref "D12") (pin "C") (pinfunction "C_C") (pintype "passive"))
      (node (ref "D13") (pin "A") (pinfunction "A_A") (pintype "passive"))
    )
    (net (code "34") (name "Net-(D13-PadC)") (class "Default")
      (node (ref "D13") (pin "C") (pinfunction "C_C") (pintype "passive"))
      (node (ref "R3") (pin "1") (pinfunction "1_1") (pintype "passive"))
    )
    (net (code "35") (name "Net-(D14-PadC)") (class "Default")
      (node (ref "D14") (pin "C") (pinfunction "C_C") (pintype "passive"))
      (node (ref "R2") (pin "2") (pinfunction "2_2") (pintype "passive"))
    )
    (net (code "36") (name "Net-(D15-PadC)") (class "Default")
      (node (ref "D15") (pin "C") (pinfunction "C_C") (pintype "passive"))
      (node (ref "R3") (pin "2") (pinfunction "2_2") (pintype "passive"))
    )
    (net (code "37") (name "Net-(D29-B)") (class "Default")
      (node (ref "D29") (pin "3") (pinfunction "B_3") (pintype "output"))
      (node (ref "R4") (pin "1") (pinfunction "1_1") (pintype "passive"))
    )
    (net (code "38") (name "Net-(D29-G)") (class "Default")
      (node (ref "D29") (pin "4") (pinfunction "G_4") (pintype "output"))
      (node (ref "R5") (pin "1") (pinfunction "1_1") (pintype "passive"))
    )
    (net (code "39") (name "Net-(D29-R)") (class "Default")
      (node (ref "D29") (pin "2") (pinfunction "R_2") (pintype "output"))
      (node (ref "R8") (pin "1") (pinfunction "1_1") (pintype "passive"))
    )
    (net (code "40") (name "Net-(F1-PadP$1)") (class "Default")
      (node (ref "F1") (pin "P$1") (pinfunction "P$1_P$1") (pintype "bidirectional"))
      (node (ref "TP3") (pin "TESTPOINT") (pinfunction "TESTPOINT_TESTPOINT") (pintype "bidirectional"))
    )
    (net (code "41") (name "Net-(J1-VCC)") (class "Default")
      (node (ref "C23") (pin "1") (pinfunction "1_1") (pintype "bidirectional"))
      (node (ref "J1") (pin "4") (pinfunction "VCC_4") (pintype "bidirectional"))
      (node (ref "R14") (pin "2") (pinfunction "2_2") (pintype "passive"))
      (node (ref "R15") (pin "2") (pinfunction "2_2") (pintype "passive"))
      (node (ref "R16") (pin "2") (pinfunction "2_2") (pintype "passive"))
      (node (ref "R26") (pin "2") (pinfunction "2_2") (pintype "passive"))
      (node (ref "U13") (pin "1") (pinfunction "VLOAD_1") (pintype "bidirectional"))
      (node (ref "U13") (pin "2") (pinfunction "VLOAD_2") (pintype "bidirectional"))
    )
    (net (code "42") (name "Net-(JP1-2)") (class "Default")
      (node (ref "JP1") (pin "VCC") (pinfunction "2_VCC") (pintype "passive"))
      (node (ref "JP2") (pin "VCC") (pinfunction "2_VCC") (pintype "passive"))
      (node (ref "R21") (pin "1") (pinfunction "1_1") (pintype "passive"))
      (node (ref "R33") (pin "1") (pinfunction "1_1") (pintype "passive"))
      (node (ref "U9") (pin "5") (pinfunction "WDS_5") (pintype "bidirectional"))
      (node (ref "U9") (pin "8") (pinfunction "VCC_8") (pintype "bidirectional"))
    )
    (net (code "43") (name "Net-(L2-P$1)") (class "Default")
      (node (ref "L2") (pin "1") (pinfunction "P$1_1") (pintype "bidirectional"))
      (node (ref "U8") (pin "2") (pinfunction "TXD_2") (pintype "bidirectional"))
    )
    (net (code "44") (name "Net-(L3-P$1)") (class "Default")
      (node (ref "L3") (pin "1") (pinfunction "P$1_1") (pintype "bidirectional"))
      (node (ref "U8") (pin "3") (pinfunction "RXD_3") (pintype "bidirectional"))
    )
    (net (code "45") (name "Net-(Q1-D)") (class "Default")
      (node (ref "Q1") (pin "3") (pinfunction "D_3") (pintype "passive"))
      (node (ref "R33") (pin "2") (pinfunction "2_2") (pintype "passive"))
      (node (ref "R42") (pin "1") (pinfunction "1_1") (pintype "passive"))
      (node (ref "R43") (pin "2") (pinfunction "2_2") (pintype "passive"))
      (node (ref "U9") (pin "1") (pinfunction "~{MR}_1") (pintype "bidirectional"))
    )
    (net (code "46") (name "Net-(Q2-D)") (class "Default")
      (node (ref "ASSY1") (pin "WKP") (pinfunction "WKP_WKP") (pintype "bidirectional"))
      (node (ref "Q2") (pin "3") (pinfunction "D_3") (pintype "passive"))
      (node (ref "R24") (pin "2") (pinfunction "2_2") (pintype "passive"))
      (node (ref "R25") (pin "1") (pinfunction "1_1") (pintype "passive"))
    )
    (net (code "47") (name "Net-(R1-Pad2)") (class "Default")
      (node (ref "R1") (pin "2") (pinfunction "2_2") (pintype "passive"))
      (node (ref "U6") (pin "AC/L") (pinfunction "AC/L_AC/L") (pintype "bidirectional"))
      (node (ref "V1") (pin "1") (pinfunction "1_1") (pintype "passive"))
    )
    (net (code "48") (name "Net-(U1-AF)") (class "Default")
      (node (ref "C3") (pin "1") (pinfunction "1_1") (pintype "bidirectional"))
      (node (ref "U1") (pin "14") (pinfunction "AF_14") (pintype "bidirectional"))
    )
    (net (code "49") (name "Net-(U1-EXTI)") (class "Default")
      (node (ref "R29") (pin "2") (pinfunction "2_2") (pintype "passive"))
      (node (ref "R30") (pin "1") (pinfunction "1_1") (pintype "passive"))
      (node (ref "U1") (pin "10") (pinfunction "EXTI_10") (pintype "bidirectional"))
    )
    (net (code "50") (name "Net-(U1-VBAT)") (class "Default")
      (node (ref "B1") (pin "+") (pinfunction "+_+") (pintype "bidirectional"))
      (node (ref "R22") (pin "1") (pinfunction "1_1") (pintype "passive"))
      (node (ref "U1") (pin "5") (pinfunction "VBAT_5") (pintype "bidirectional"))
    )
    (net (code "51") (name "Net-(U1-XI)") (class "Default")
      (node (ref "U1") (pin "16") (pinfunction "XI_16") (pintype "bidirectional"))
      (node (ref "X2") (pin "1") (pinfunction "1_1") (pintype "bidirectional"))
    )
    (net (code "52") (name "Net-(U1-XO)") (class "Default")
      (node (ref "U1") (pin "15") (pinfunction "XO_15") (pintype "bidirectional"))
      (node (ref "X2") (pin "2") (pinfunction "2_2") (pintype "bidirectional"))
    )
    (net (code "53") (name "Net-(U2A--)") (class "Default")
      (node (ref "R11") (pin "2") (pinfunction "2_2") (pintype "passive"))
      (node (ref "R36") (pin "2") (pinfunction "2_2") (pintype "passive"))
      (node (ref "R37") (pin "2") (pinfunction "2_2") (pintype "passive"))
      (node (ref "U2") (pin "1") (pinfunction "-_1") (pintype "bidirectional"))
    )
    (net (code "54") (name "Net-(U2B--)") (class "Default")
      (node (ref "R40") (pin "1") (pinfunction "1_1") (pintype "passive"))
      (node (ref "R41") (pin "1") (pinfunction "1_1") (pintype "passive"))
      (node (ref "R7") (pin "1") (pinfunction "1_1") (pintype "passive"))
      (node (ref "U2") (pin "5") (pinfunction "-_5") (pintype "bidirectional"))
    )
    (net (code "55") (name "Net-(U2C--)") (class "Default")
      (node (ref "R10") (pin "1") (pinfunction "1_1") (pintype "passive"))
      (node (ref "R34") (pin "2") (pinfunction "2_2") (pintype "passive"))
      (node (ref "R35") (pin "2") (pinfunction "2_2") (pintype "passive"))
      (node (ref "U2") (pin "8") (pinfunction "-_8") (pintype "bidirectional"))
    )
    (net (code "56") (name "Net-(U2D--)") (class "Default")
      (node (ref "R38") (pin "1") (pinfunction "1_1") (pintype "passive"))
      (node (ref "R39") (pin "1") (pinfunction "1_1") (pintype "passive"))
      (node (ref "R6") (pin "1") (pinfunction "1_1") (pintype "passive"))
      (node (ref "U2") (pin "12") (pinfunction "-_12") (pintype "bidirectional"))
    )
    (net (code "57") (name "Net-(U3-AI)") (class "Default")
      (node (ref "L1") (pin "1") (pinfunction "1_1") (pintype "bidirectional"))
      (node (ref "U3") (pin "5") (pinfunction "AI_5") (pintype "input"))
    )
    (net (code "58") (name "Net-(U3-AO)") (class "Default")
      (node (ref "U3") (pin "3") (pinfunction "AO_3") (pintype "output"))
      (node (ref "U5") (pin "1") (pinfunction "INPUT_1") (pintype "input"))
    )
    (net (code "59") (name "Net-(U5-OUTPUT)") (class "Default")
      (node (ref "U5") (pin "4") (pinfunction "OUTPUT_4") (pintype "bidirectional"))
      (node (ref "U8") (pin "11") (pinfunction "RF_IN_11") (pintype "bidirectional"))
    )
    (net (code "60") (name "Net-(U9-SRT)") (class "Default")
      (node (ref "C17") (pin "1") (pinfunction "1_1") (pintype "bidirectional"))
      (node (ref "U9") (pin "3") (pinfunction "SRT_3") (pintype "bidirectional"))
    )
    (net (code "61") (name "Net-(U9-SWT)") (class "Default")
      (node (ref "C22") (pin "1") (pinfunction "1_1") (pintype "bidirectional"))
      (node (ref "U9") (pin "2") (pinfunction "SWT_2") (pintype "bidirectional"))
    )
    (net (code "62") (name "Net-(U10-P0)") (class "Default")
      (node (ref "R8") (pin "2") (pinfunction "2_2") (pintype "passive"))
      (node (ref "U10") (pin "2") (pinfunction "P0_2") (pintype "bidirectional"))
    )
    (net (code "63") (name "Net-(U10-P1)") (class "Default")
      (node (ref "R4") (pin "2") (pinfunction "2_2") (pintype "passive"))
      (node (ref "U10") (pin "3") (pinfunction "P1_3") (pintype "bidirectional"))
    )
    (net (code "64") (name "Net-(U10-P2)") (class "Default")
      (node (ref "R5") (pin "2") (pinfunction "2_2") (pintype "passive"))
      (node (ref "U10") (pin "4") (pinfunction "P2_4") (pintype "bidirectional"))
    )
    (net (code "65") (name "Net-(U15-PC14{slash}OSC32IN)") (class "Default")
      (node (ref "C1") (pin "2") (pinfunction "2_2") (pintype "bidirectional"))
      (node (ref "U15") (pin "2") (pinfunction "PC14/OSC32IN_2") (pintype "bidirectional"))
      (node (ref "X1") (pin "B") (pinfunction "2_B") (pintype "bidirectional"))
    )
    (net (code "66") (name "Net-(U15-PC15{slash}OSC32OUT)") (class "Default")
      (node (ref "C2") (pin "2") (pinfunction "2_2") (pintype "bidirectional"))
      (node (ref "U15") (pin "3") (pinfunction "PC15/OSC32OUT_3") (pintype "bidirectional"))
      (node (ref "X1") (pin "A") (pinfunction "1_A") (pintype "bidirectional"))
    )
    (net (code "67") (name "PARTICLE_RST") (class "Default")
      (node (ref "ASSY1") (pin "D2") (pinfunction "D2_D2") (pintype "bidirectional"))
      (node (ref "Q1") (pin "1") (pinfunction "G_1") (pintype "passive"))
      (node (ref "R44") (pin "1") (pinfunction "1_1") (pintype "passive"))
    )
    (net (code "68") (name "REF_1V5") (class "Default")
      (node (ref "C10") (pin "1") (pinfunction "1_1") (pintype "bidirectional"))
      (node (ref "C11") (pin "1") (pinfunction "1_1") (pintype "bidirectional"))
      (node (ref "C12") (pin "1") (pinfunction "1_1") (pintype "bidirectional"))
      (node (ref "C13") (pin "1") (pinfunction "1_1") (pintype "bidirectional"))
      (node (ref "U11") (pin "1") (pinfunction "VBIAS_1") (pintype "input"))
      (node (ref "U2") (pin "11") (pinfunction "+_11") (pintype "bidirectional"))
      (node (ref "U2") (pin "2") (pinfunction "+_2") (pintype "bidirectional"))
      (node (ref "U2") (pin "4") (pinfunction "+_4") (pintype "bidirectional"))
      (node (ref "U2") (pin "9") (pinfunction "+_9") (pintype "bidirectional"))
    )
    (net (code "69") (name "REF_3V") (class "Default")
      (node (ref "C14") (pin "1") (pinfunction "1_1") (pintype "bidirectional"))
      (node (ref "C19") (pin "1") (pinfunction "1_1") (pintype "bidirectional"))
      (node (ref "U11") (pin "5") (pinfunction "VREF_5") (pintype "output"))
      (node (ref "U15") (pin "5") (pinfunction "VDDA/VREF_5") (pintype "bidirectional"))
      (node (ref "U2") (pin "3") (pinfunction "V+_3") (pintype "bidirectional"))
    )
    (net (code "70") (name "SD_ENABLE") (class "Default")
      (node (ref "ASSY1") (pin "C2") (pinfunction "C2_C2") (pintype "bidirectional"))
      (node (ref "R27") (pin "2") (pinfunction "2_2") (pintype "passive"))
      (node (ref "U13") (pin "3") (pinfunction "EN_3") (pintype "bidirectional"))
    )
    (net (code "71") (name "SD_MISO") (class "Default")
      (node (ref "ASSY1") (pin "A4") (pinfunction "A4_A4") (pintype "bidirectional"))
      (node (ref "J1") (pin "7") (pinfunction "DATA0/MISO_7") (pintype "bidirectional"))
      (node (ref "R16") (pin "1") (pinfunction "1_1") (pintype "passive"))
      (node (ref "U1") (pin "6") (pinfunction "SDO_6") (pintype "bidirectional"))
    )
    (net (code "72") (name "SD_MOSI") (class "Default")
      (node (ref "ASSY1") (pin "A5") (pinfunction "A5_A5") (pintype "bidirectional"))
      (node (ref "J1") (pin "3") (pinfunction "CMD/MOSI_3") (pintype "bidirectional"))
      (node (ref "R14") (pin "1") (pinfunction "1_1") (pintype "passive"))
      (node (ref "U1") (pin "9") (pinfunction "SDI_9") (pintype "bidirectional"))
    )
    (net (code "73") (name "SD_SCLK") (class "Default")
      (node (ref "ASSY1") (pin "A3") (pinfunction "A3_A3") (pintype "bidirectional"))
      (node (ref "J1") (pin "5") (pinfunction "CLK_5") (pintype "bidirectional"))
      (node (ref "U1") (pin "7") (pinfunction "SCL_7") (pintype "bidirectional"))
    )
    (net (code "74") (name "SENSORS_SCL") (class "Default")
      (node (ref "ASSY1") (pin "D1") (pinfunction "D1_D1") (pintype "bidirectional"))
      (node (ref "R17") (pin "1") (pinfunction "1_1") (pintype "passive"))
      (node (ref "U10") (pin "12") (pinfunction "SCL_12") (pintype "input"))
      (node (ref "U16") (pin "8") (pinfunction "SCL_B_8") (pintype "bidirectional"))
      (node (ref "U7") (pin "1") (pinfunction "SCL/SPC_1") (pintype "bidirectional"))
    )
    (net (code "75") (name "SENSORS_SDA") (class "Default")
      (node (ref "ASSY1") (pin "D0") (pinfunction "D0_D0") (pintype "bidirectional"))
      (node (ref "R13") (pin "1") (pinfunction "1_1") (pintype "passive"))
      (node (ref "U10") (pin "13") (pinfunction "SDA_13") (pintype "bidirectional"))
      (node (ref "U16") (pin "1") (pinfunction "SDA_B_1") (pintype "bidirectional"))
      (node (ref "U7") (pin "4") (pinfunction "MOSI/SDA_4") (pintype "bidirectional"))
    )
    (net (code "76") (name "SERIAL_NUM") (class "Default")
      (node (ref "ASSY1") (pin "B0") (pinfunction "B0_B0") (pintype "bidirectional"))
      (node (ref "R12") (pin "2") (pinfunction "2_2") (pintype "passive"))
      (node (ref "U4") (pin "2") (pinfunction "DATA_2") (pintype "input"))
    )
    (net (code "77") (name "SWDCLK") (class "Default")
      (node (ref "J2") (pin "4") (pinfunction "SWDCLK_4") (pintype "bidirectional"))
      (node (ref "U15") (pin "24") (pinfunction "PA14/SWDCLK_24") (pintype "bidirectional"))
    )
    (net (code "78") (name "SWDIO") (class "Default")
      (node (ref "J2") (pin "2") (pinfunction "SWDIO_2") (pintype "bidirectional"))
      (node (ref "U15") (pin "23") (pinfunction "PA13/SWDIO_23") (pintype "bidirectional"))
    )
    (net (code "79") (name "VCC") (class "Default")
      (node (ref "ASSY1") (pin "3V3") (pinfunction "3V3_3V3") (pintype "power_in"))
      (node (ref "C18") (pin "1") (pinfunction "1_1") (pintype "bidirectional"))
      (node (ref "C25") (pin "1") (pinfunction "1_1") (pintype "bidirectional"))
      (node (ref "C9") (pin "1") (pinfunction "1_1") (pintype "bidirectional"))
      (node (ref "D29") (pin "1") (pinfunction "VDD_1") (pintype "bidirectional"))
      (node (ref "Q2") (pin "2") (pinfunction "S_2") (pintype "passive"))
      (node (ref "R12") (pin "1") (pinfunction "1_1") (pintype "passive"))
      (node (ref "R13") (pin "2") (pinfunction "2_2") (pintype "passive"))
      (node (ref "R17") (pin "2") (pinfunction "2_2") (pintype "passive"))
      (node (ref "R19") (pin "1") (pinfunction "1_1") (pintype "passive"))
      (node (ref "R20") (pin "1") (pinfunction "1_1") (pintype "passive"))
      (node (ref "R32") (pin "1") (pinfunction "1_1") (pintype "passive"))
      (node (ref "U1") (pin "13") (pinfunction "VCC_13") (pintype "bidirectional"))
      (node (ref "U10") (pin "1") (pinfunction "AD2_1") (pintype "input"))
      (node (ref "U10") (pin "14") (pinfunction "V+_14") (pintype "power_in"))
      (node (ref "U10") (pin "15") (pinfunction "AD0_15") (pintype "input"))
      (node (ref "U10") (pin "16") (pinfunction "AD1_16") (pintype "input"))
      (node (ref "U12") (pin "5") (pinfunction "VSUPP_5") (pintype "bidirectional"))
      (node (ref "U12") (pin "6") (pinfunction "VSUPP_6") (pintype "bidirectional"))
      (node (ref "U13") (pin "5") (pinfunction "VSUPP_5") (pintype "bidirectional"))
      (node (ref "U13") (pin "6") (pinfunction "VSUPP_6") (pintype "bidirectional"))
      (node (ref "U14") (pin "5") (pinfunction "VSUPP_5") (pintype "bidirectional"))
      (node (ref "U14") (pin "6") (pinfunction "VSUPP_6") (pintype "bidirectional"))
      (node (ref "U16") (pin "7") (pinfunction "VCCB_7") (pintype "power_in"))
      (node (ref "U7") (pin "10") (pinfunction "VDD_IO_10") (pintype "bidirectional"))
      (node (ref "U7") (pin "2") (pinfunction "CS_2") (pintype "bidirectional"))
      (node (ref "U7") (pin "9") (pinfunction "VCC_9") (pintype "bidirectional"))
    )
    (net (code "80") (name "VCC_RF") (class "Default")
      (node (ref "C4") (pin "2") (pinfunction "2_2") (pintype "bidirectional"))
      (node (ref "U3") (pin "2") (pinfunction "VCC_2") (pintype "power_in"))
      (node (ref "U3") (pin "6") (pinfunction "PON_6") (pintype "input"))
      (node (ref "U8") (pin "14") (pinfunction "VCC_RF_14") (pintype "bidirectional"))
    )
    (net (code "81") (name "VOLTAGE_COPROC_RX") (class "Default")
      (node (ref "ASSY1") (pin "C1") (pinfunction "C1_C1") (pintype "bidirectional"))
      (node (ref "U15") (pin "30") (pinfunction "PB7_30") (pintype "bidirectional"))
    )
    (net (code "82") (name "VOLTAGE_COPROC_TX") (class "Default")
      (node (ref "ASSY1") (pin "C0") (pinfunction "C0_C0") (pintype "bidirectional"))
      (node (ref "U15") (pin "29") (pinfunction "PB6_29") (pintype "bidirectional"))
    )
    (net (code "83") (name "WDI") (class "Default")
      (node (ref "ASSY1") (pin "DAC") (pinfunction "DAC_DAC") (pintype "bidirectional"))
      (node (ref "R18") (pin "1") (pinfunction "1_1") (pintype "passive"))
      (node (ref "U1") (pin "2") (pinfunction "WDI_2") (pintype "bidirectional"))
      (node (ref "U9") (pin "6") (pinfunction "WDI_6") (pintype "bidirectional"))
    )
    (net (code "84") (name "unconnected-(ASSY1-PadVBAT)") (class "Default")
      (node (ref "ASSY1") (pin "VBAT") (pinfunction "VBAT_VBAT") (pintype "passive"))
    )
    (net (code "85") (name "unconnected-(J1-DATA1{slash}RSV-Pad8)") (class "Default")
      (node (ref "J1") (pin "8") (pinfunction "DATA1/RSV_8") (pintype "bidirectional"))
    )
    (net (code "86") (name "unconnected-(J1-DATA2{slash}NC-Pad1)") (class "Default")
      (node (ref "J1") (pin "1") (pinfunction "DATA2/NC_1") (pintype "bidirectional"))
    )
    (net (code "87") (name "unconnected-(J2-SWO-Pad6)") (class "Default")
      (node (ref "J2") (pin "6") (pinfunction "SWO_6") (pintype "bidirectional"))
    )
    (net (code "88") (name "unconnected-(U1-CLKOUT{slash}~{IRQ3}-Pad8)") (class "Default")
      (node (ref "U1") (pin "8") (pinfunction "CLKOUT/~{IRQ3}_8") (pintype "bidirectional"))
    )
    (net (code "89") (name "unconnected-(U1-~{RST}-Pad1)") (class "Default")
      (node (ref "U1") (pin "1") (pinfunction "~{RST}_1") (pintype "bidirectional"))
    )
    (net (code "90") (name "unconnected-(U4-NC-Pad6)") (class "Default")
      (node (ref "U4") (pin "6") (pinfunction "NC_6") (pintype "no_connect"))
    )
    (net (code "91") (name "unconnected-(U4-NC_2-Pad3)") (class "Default")
      (node (ref "U4") (pin "3") (pinfunction "NC_2_3") (pintype "no_connect"))
    )
    (net (code "92") (name "unconnected-(U4-NC_3-Pad4)") (class "Default")
      (node (ref "U4") (pin "4") (pinfunction "NC_3_4") (pintype "no_connect"))
    )
    (net (code "93") (name "unconnected-(U4-NC_4-Pad5)") (class "Default")
      (node (ref "U4") (pin "5") (pinfunction "NC_4_5") (pintype "no_connect"))
    )
    (net (code "94") (name "unconnected-(U7-INT2-Pad11)") (class "Default")
      (node (ref "U7") (pin "11") (pinfunction "INT2_11") (pintype "bidirectional"))
    )
    (net (code "95") (name "unconnected-(U8-EXTINT-Pad5)") (class "Default")
      (node (ref "U8") (pin "5") (pinfunction "EXTINT_5") (pintype "bidirectional"))
    )
    (net (code "96") (name "unconnected-(U8-LNA_EN-Pad13)") (class "Default")
      (node (ref "U8") (pin "13") (pinfunction "LNA_EN_13") (pintype "bidirectional"))
    )
    (net (code "97") (name "unconnected-(U8-SCL-Pad17)") (class "Default")
      (node (ref "U8") (pin "17") (pinfunction "SCL_17") (pintype "bidirectional"))
    )
    (net (code "98") (name "unconnected-(U8-SDA-Pad16)") (class "Default")
      (node (ref "U8") (pin "16") (pinfunction "SDA_16") (pintype "bidirectional"))
    )
    (net (code "99") (name "unconnected-(U8-V_ANT-Pad15)") (class "Default")
      (node (ref "U8") (pin "15") (pinfunction "V_ANT_15") (pintype "bidirectional"))
    )
    (net (code "100") (name "unconnected-(U8-~{RESET}-Pad9)") (class "Default")
      (node (ref "U8") (pin "9") (pinfunction "~{RESET}_9") (pintype "bidirectional"))
    )
    (net (code "101") (name "unconnected-(U8-~{SAFEBOOT}-Pad18)") (class "Default")
      (node (ref "U8") (pin "18") (pinfunction "~{SAFEBOOT}_18") (pintype "bidirectional"))
    )
    (net (code "102") (name "unconnected-(U10-P3-Pad5)") (class "Default")
      (node (ref "U10") (pin "5") (pinfunction "P3_5") (pintype "bidirectional"))
    )
    (net (code "103") (name "unconnected-(U10-P4-Pad7)") (class "Default")
      (node (ref "U10") (pin "7") (pinfunction "P4_7") (pintype "bidirectional"))
    )
    (net (code "104") (name "unconnected-(U10-P5-Pad8)") (class "Default")
      (node (ref "U10") (pin "8") (pinfunction "P5_8") (pintype "bidirectional"))
    )
    (net (code "105") (name "unconnected-(U10-P6-Pad9)") (class "Default")
      (node (ref "U10") (pin "9") (pinfunction "P6_9") (pintype "bidirectional"))
    )
    (net (code "106") (name "unconnected-(U10-P7-Pad10)") (class "Default")
      (node (ref "U10") (pin "10") (pinfunction "P7_10") (pintype "bidirectional"))
    )
    (net (code "107") (name "unconnected-(U10-~{INT{slash}08}-Pad11)") (class "Default")
      (node (ref "U10") (pin "11") (pinfunction "~{INT/08}_11") (pintype "output"))
    )
    (net (code "108") (name "unconnected-(U15-PA2-Pad8)") (class "Default")
      (node (ref "U15") (pin "8") (pinfunction "PA2_8") (pintype "bidirectional"))
    )
    (net (code "109") (name "unconnected-(U15-PA5-Pad11)") (class "Default")
      (node (ref "U15") (pin "11") (pinfunction "PA5_11") (pintype "bidirectional"))
    )
    (net (code "110") (name "unconnected-(U15-PA6-Pad12)") (class "Default")
      (node (ref "U15") (pin "12") (pinfunction "PA6_12") (pintype "bidirectional"))
    )
    (net (code "111") (name "unconnected-(U15-PA7-Pad13)") (class "Default")
      (node (ref "U15") (pin "13") (pinfunction "PA7_13") (pintype "bidirectional"))
    )
    (net (code "112") (name "unconnected-(U15-PA8-Pad18)") (class "Default")
      (node (ref "U15") (pin "18") (pinfunction "PA8_18") (pintype "bidirectional"))
    )
    (net (code "113") (name "unconnected-(U15-PA11-Pad21)") (class "Default")
      (node (ref "U15") (pin "21") (pinfunction "PA11_21") (pintype "bidirectional"))
    )
    (net (code "114") (name "unconnected-(U15-PA12-Pad22)") (class "Default")
      (node (ref "U15") (pin "22") (pinfunction "PA12_22") (pintype "bidirectional"))
    )
    (net (code "115") (name "unconnected-(U15-PA15{slash}JTDI-Pad25)") (class "Default")
      (node (ref "U15") (pin "25") (pinfunction "PA15/JTDI_25") (pintype "bidirectional"))
    )
    (net (code "116") (name "unconnected-(U15-PB0-Pad14)") (class "Default")
      (node (ref "U15") (pin "14") (pinfunction "PB0_14") (pintype "bidirectional"))
    )
    (net (code "117") (name "unconnected-(U17-NR-Pad4)") (class "Default")
      (node (ref "U17") (pin "4") (pinfunction "NR_4") (pintype "passive"))
    )
    (net (code "118") (name "~{EXTERNAL_RST}") (class "Default")
      (node (ref "ASSY1") (pin "RST") (pinfunction "RST_RST") (pintype "bidirectional"))
      (node (ref "R21") (pin "2") (pinfunction "2_2") (pintype "passive"))
      (node (ref "U9") (pin "7") (pinfunction "~{RESET}_7") (pintype "bidirectional"))
    )
    (net (code "119") (name "~{RST}") (class "Default")
      (node (ref "J2") (pin "3") (pinfunction "~{RESET}_3") (pintype "bidirectional"))
      (node (ref "S1") (pin "2") (pinfunction "P$2_2") (pintype "passive"))
      (node (ref "U15") (pin "4") (pinfunction "~{RST}_4") (pintype "bidirectional"))
    )
    (net (code "120") (name "~{RTC_CS}") (class "Default")
      (node (ref "ASSY1") (pin "C5") (pinfunction "C5_C5") (pintype "bidirectional"))
      (node (ref "R20") (pin "2") (pinfunction "2_2") (pintype "passive"))
      (node (ref "R22") (pin "2") (pinfunction "2_2") (pintype "passive"))
      (node (ref "U1") (pin "12") (pinfunction "~{CS}_12") (pintype "bidirectional"))
    )
    (net (code "121") (name "~{RTC_INT1}") (class "Default")
      (node (ref "ASSY1") (pin "D5") (pinfunction "D5_D5") (pintype "bidirectional"))
      (node (ref "R19") (pin "2") (pinfunction "2_2") (pintype "passive"))
      (node (ref "U1") (pin "11") (pinfunction "FOUT/~{IRQ1}_11") (pintype "bidirectional"))
    )
    (net (code "122") (name "~{RTC_INT2}") (class "Default")
      (node (ref "ASSY1") (pin "D3") (pinfunction "D3_D3") (pintype "bidirectional"))
      (node (ref "Q2") (pin "1") (pinfunction "G_1") (pintype "passive"))
      (node (ref "R32") (pin "2") (pinfunction "2_2") (pintype "passive"))
      (node (ref "U1") (pin "4") (pinfunction "~{IRQ2}_4") (pintype "bidirectional"))
    )
    (net (code "123") (name "~{SD_CS}") (class "Default")
      (node (ref "ASSY1") (pin "A2") (pinfunction "A2_A2") (pintype "bidirectional"))
      (node (ref "J1") (pin "2") (pinfunction "DATA3-CD/CS_N_2") (pintype "bidirectional"))
      (node (ref "R15") (pin "1") (pinfunction "1_1") (pintype "passive"))
    )
    (net (code "124") (name "~{SD_DETECT}") (class "Default")
      (node (ref "ASSY1") (pin "D6") (pinfunction "D6_D6") (pintype "bidirectional"))
      (node (ref "J1") (pin "A") (pinfunction "A_A") (pintype "bidirectional"))
      (node (ref "R26") (pin "1") (pinfunction "1_1") (pintype "passive"))
    )
  )
)
